# Sheet1.net
KiCad netlist of a schematic drawn in Altium Designer
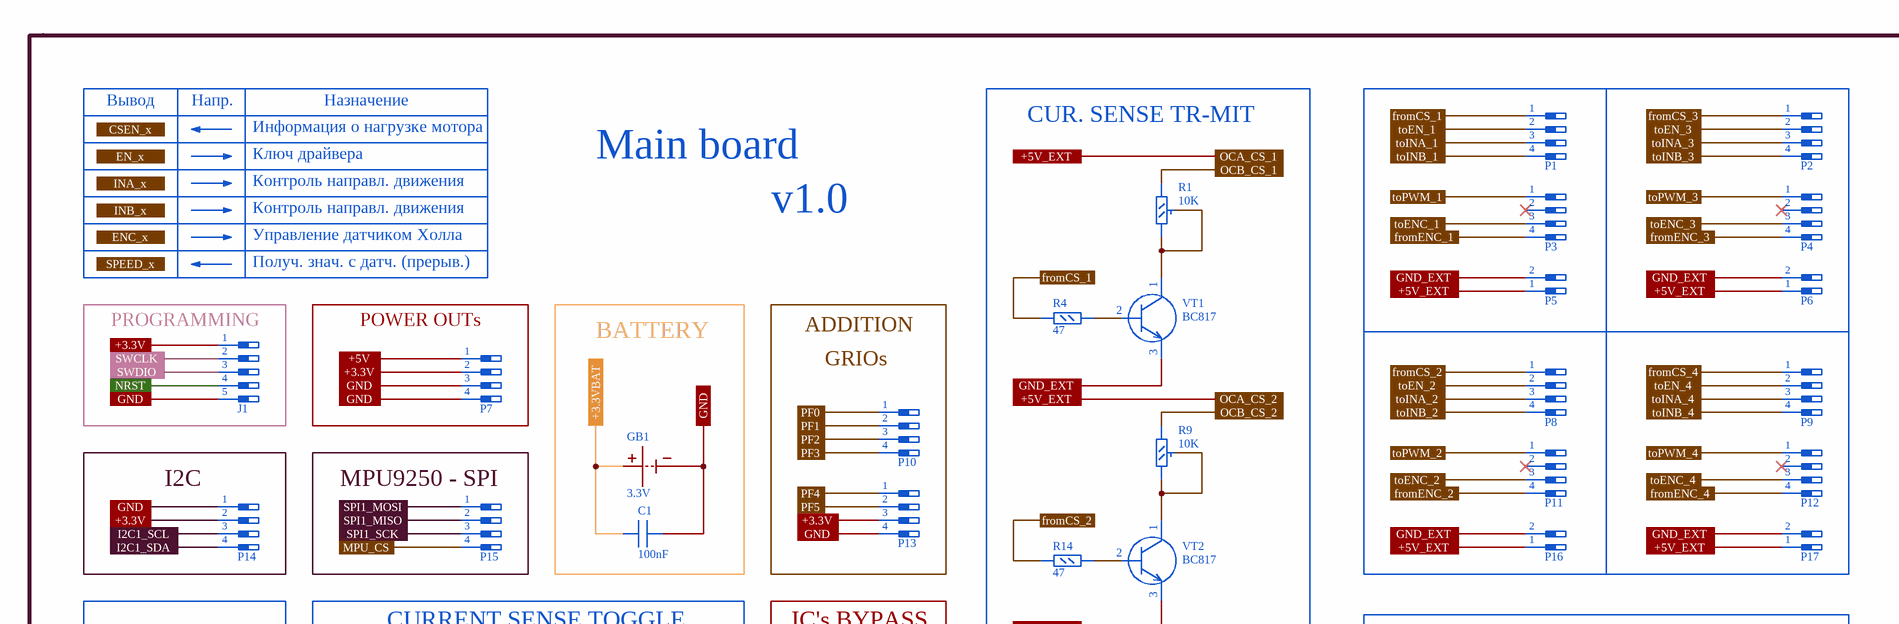
[diagram p0: Sheet1.SchDoc, top left]
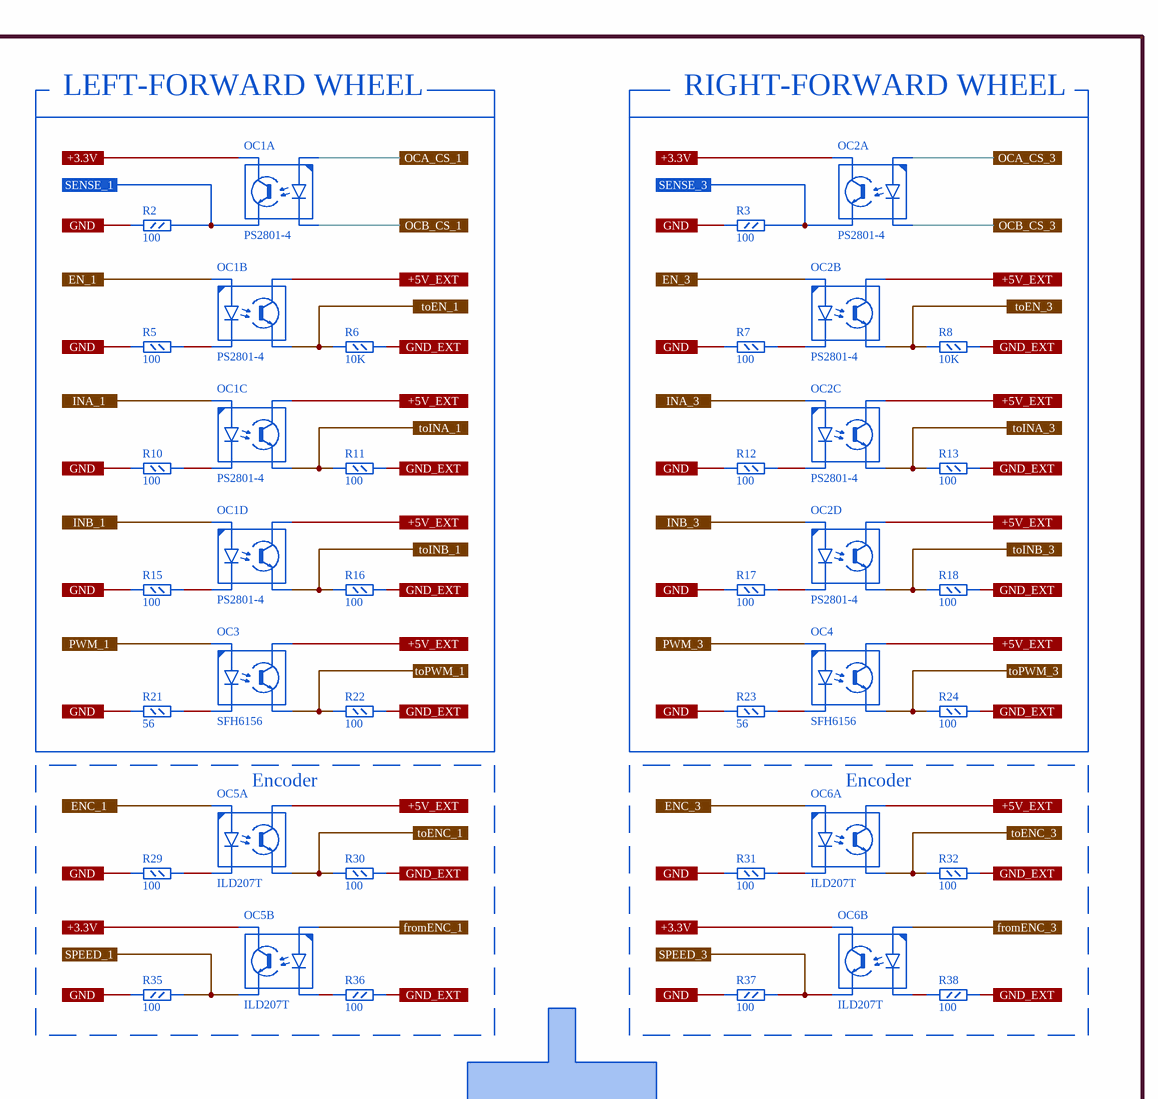
[diagram p1: Sheet1.SchDoc, top right]
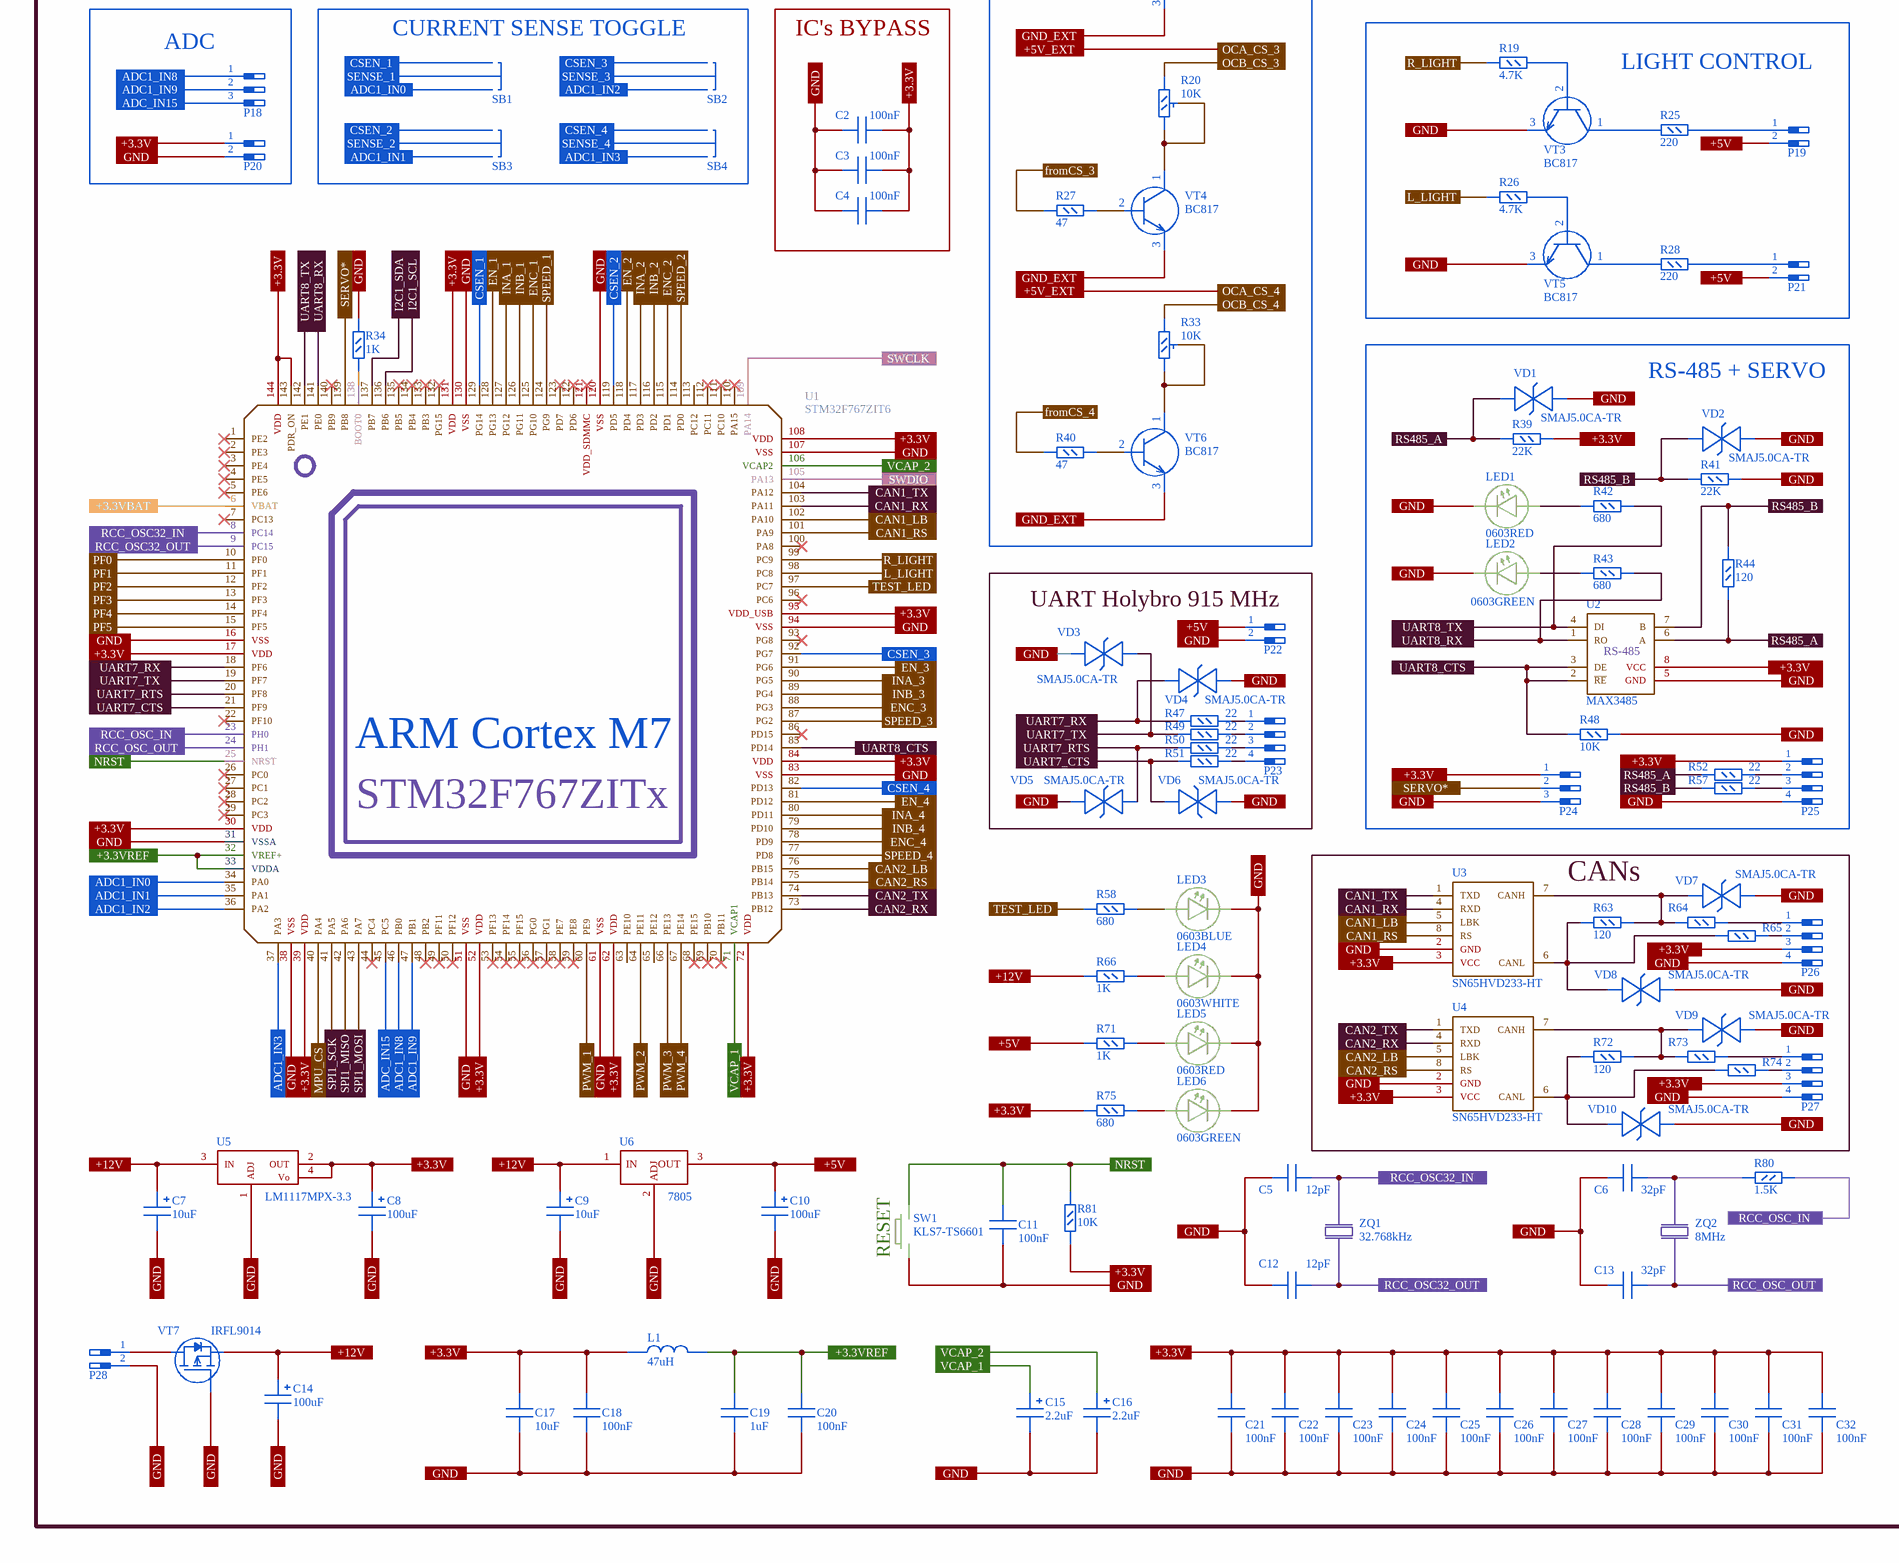
[diagram p2: Sheet1.SchDoc, bottom left]
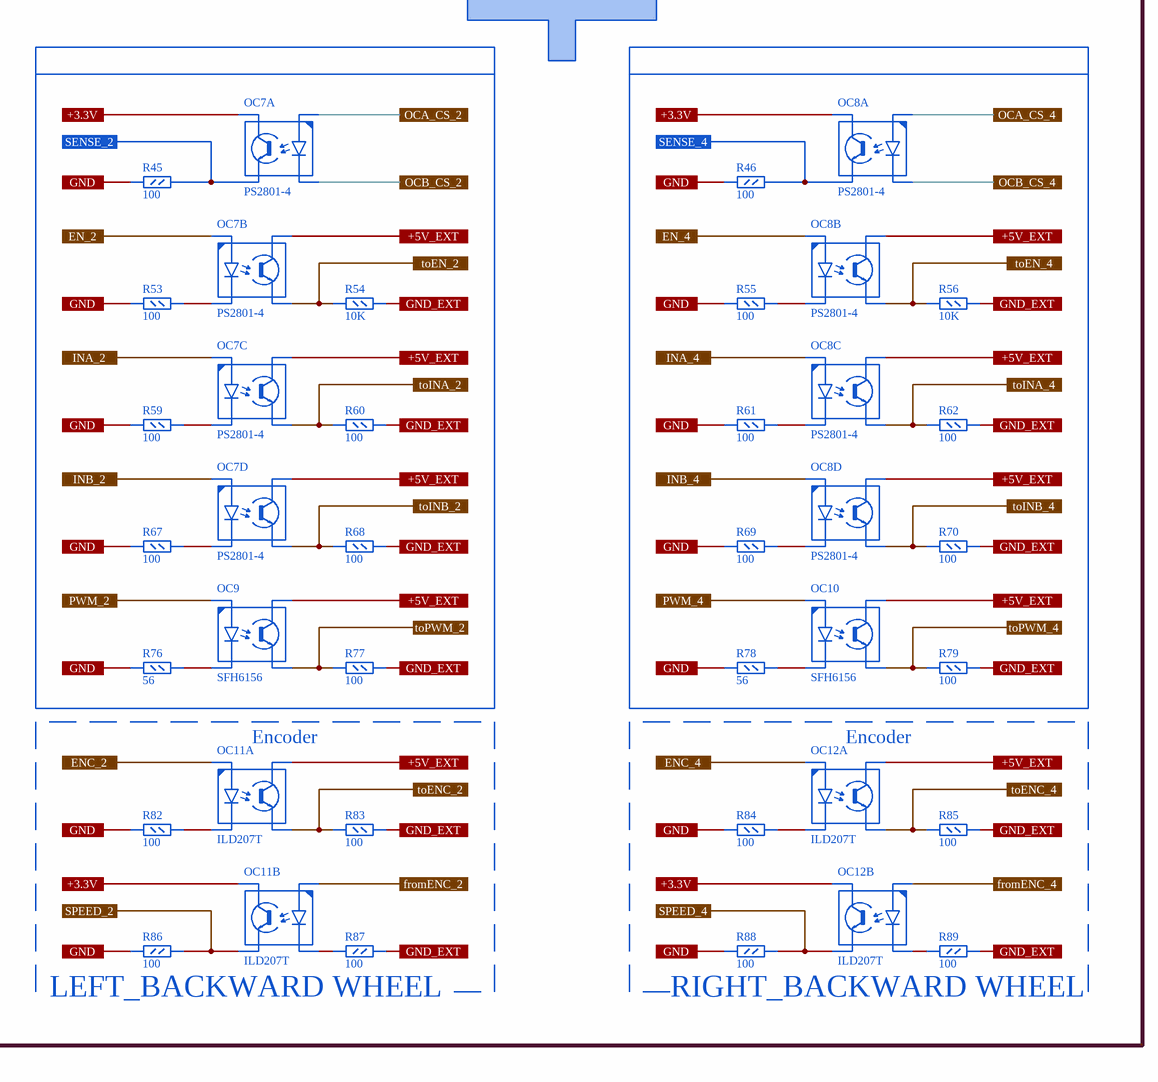
[diagram p3: Sheet1.SchDoc, bottom right]

(export (version "E")
  (design (tool "Eeschema 10.0.6"))
  (components
    (comp (ref "C1") (value "100nF") (footprint "C0603") (libsource (lib "CustomMillLib_Col") (part "Cap")))
    (comp (ref "C2") (value "100nF") (footprint "C0603") (libsource (lib "CustomMillLib_Col") (part "Cap")))
    (comp (ref "C3") (value "100nF") (footprint "C0603") (libsource (lib "CustomMillLib_Col") (part "Cap")))
    (comp (ref "C4") (value "100nF") (footprint "C0603") (libsource (lib "CustomMillLib_Col") (part "Cap")))
    (comp (ref "C5") (value "12pF") (footprint "C0603") (libsource (lib "CustomMillLib_Col") (part "Cap")))
    (comp (ref "C6") (value "32pF") (footprint "C0603") (libsource (lib "CustomMillLib_Col") (part "Cap")))
    (comp (ref "C7")
      (value "10uF")
      (footprint "CAP-ALSMD-4x5.4")
      (libsource (lib "CustomMillLib_Col") (part "Cap_Pol"))
    )
    (comp (ref "C8")
      (value "100uF")
      (footprint "CAP-ALSMD-6.3x5.4")
      (libsource (lib "CustomMillLib_Col") (part "Cap_Pol"))
    )
    (comp (ref "C9")
      (value "10uF")
      (footprint "CAP-ALSMD-4x5.4")
      (libsource (lib "CustomMillLib_Col") (part "Cap_Pol"))
    )
    (comp (ref "C10")
      (value "100uF")
      (footprint "CAP-ALSMD-6.3x5.4")
      (libsource (lib "CustomMillLib_Col") (part "Cap_Pol"))
    )
    (comp (ref "C11") (value "100nF") (footprint "C0603") (libsource (lib "CustomMillLib_Col") (part "Cap")))
    (comp (ref "C12") (value "12pF") (footprint "C0603") (libsource (lib "CustomMillLib_Col") (part "Cap")))
    (comp (ref "C13") (value "32pF") (footprint "C0603") (libsource (lib "CustomMillLib_Col") (part "Cap")))
    (comp (ref "C14")
      (value "100uF")
      (footprint "CAP-ALSMD-6.3x5.4")
      (libsource (lib "CustomMillLib_Col") (part "Cap_Pol"))
    )
    (comp (ref "C15")
      (value "2.2uF")
      (footprint "CAP-ALSMD-4x5.4")
      (libsource (lib "CustomMillLib_Col") (part "Cap_Pol"))
    )
    (comp (ref "C16")
      (value "2.2uF")
      (footprint "CAP-ALSMD-4x5.4")
      (libsource (lib "CustomMillLib_Col") (part "Cap_Pol"))
    )
    (comp (ref "C17") (value "10uF") (footprint "C0805") (libsource (lib "CustomMillLib_Col") (part "Cap")))
    (comp (ref "C18") (value "100nF") (footprint "C0603") (libsource (lib "CustomMillLib_Col") (part "Cap")))
    (comp (ref "C19") (value "1uF") (footprint "C0805") (libsource (lib "CustomMillLib_Col") (part "Cap")))
    (comp (ref "C20") (value "100nF") (footprint "C0603") (libsource (lib "CustomMillLib_Col") (part "Cap")))
    (comp (ref "C21") (value "100nF") (footprint "C0603") (libsource (lib "CustomMillLib_Col") (part "Cap")))
    (comp (ref "C22") (value "100nF") (footprint "C0603") (libsource (lib "CustomMillLib_Col") (part "Cap")))
    (comp (ref "C23") (value "100nF") (footprint "C0603") (libsource (lib "CustomMillLib_Col") (part "Cap")))
    (comp (ref "C24") (value "100nF") (footprint "C0603") (libsource (lib "CustomMillLib_Col") (part "Cap")))
    (comp (ref "C25") (value "100nF") (footprint "C0603") (libsource (lib "CustomMillLib_Col") (part "Cap")))
    (comp (ref "C26") (value "100nF") (footprint "C0603") (libsource (lib "CustomMillLib_Col") (part "Cap")))
    (comp (ref "C27") (value "100nF") (footprint "C0603") (libsource (lib "CustomMillLib_Col") (part "Cap")))
    (comp (ref "C28") (value "100nF") (footprint "C0603") (libsource (lib "CustomMillLib_Col") (part "Cap")))
    (comp (ref "C29") (value "100nF") (footprint "C0603") (libsource (lib "CustomMillLib_Col") (part "Cap")))
    (comp (ref "C30") (value "100nF") (footprint "C0603") (libsource (lib "CustomMillLib_Col") (part "Cap")))
    (comp (ref "C31") (value "100nF") (footprint "C0603") (libsource (lib "CustomMillLib_Col") (part "Cap")))
    (comp (ref "C32") (value "100nF") (footprint "C0603") (libsource (lib "CustomMillLib_Col") (part "Cap")))
    (comp (ref "GB1")
      (value "3.3V")
      (footprint "CR1616-SMD")
      (libsource (lib "PowerSupplies_Col") (part "Battery"))
    )
    (comp (ref "J1") (value "1x05") (footprint "5X1F") (libsource (lib "Connectors_Col") (part "1x05")))
    (comp (ref "L1")
      (value "47uH")
      (footprint "L0805")
      (libsource (lib "CustomMillLib_Col") (part "Inductor"))
    )
    (comp (ref "LED1")
      (value "0603RED")
      (footprint "LED0603")
      (libsource (lib "CustomMillLib_Col") (part "LED"))
    )
    (comp (ref "LED2")
      (value "0603GREEN")
      (footprint "LED0603")
      (libsource (lib "CustomMillLib_Col") (part "LED"))
    )
    (comp (ref "LED3")
      (value "0603BLUE")
      (footprint "LED0603")
      (libsource (lib "CustomMillLib_Col") (part "LED"))
    )
    (comp (ref "LED4")
      (value "0603WHITE")
      (footprint "LED0603")
      (libsource (lib "CustomMillLib_Col") (part "LED"))
    )
    (comp (ref "LED5")
      (value "0603RED")
      (footprint "LED0603")
      (libsource (lib "CustomMillLib_Col") (part "LED"))
    )
    (comp (ref "LED6")
      (value "0603GREEN")
      (footprint "LED0603")
      (libsource (lib "CustomMillLib_Col") (part "LED"))
    )
    (comp (ref "OC1") (value "PS2801-4") (footprint "SOP16") (libsource (lib "") (part "Optocoupler-4_1")))
    (comp (ref "OC2")
      (value "PS2801-4")
      (footprint "SOP16")
      (libsource (lib "CustomMillLib_Col") (part "Optocoupler-4"))
    )
    (comp (ref "OC3")
      (value "SFH6156")
      (footprint "SMD-4 (WIDE PINS)")
      (libsource (lib "CustomMillLib_Col") (part "Optocoupler"))
    )
    (comp (ref "OC4")
      (value "SFH6156")
      (footprint "SMD-4 (WIDE PINS)")
      (libsource (lib "CustomMillLib_Col") (part "Optocoupler"))
    )
    (comp (ref "OC5") (value "ILD207T") (footprint "SOIC8") (libsource (lib "") (part "Optocoupler-2_1")))
    (comp (ref "OC6")
      (value "ILD207T")
      (footprint "SOIC8")
      (libsource (lib "CustomMillLib_Col") (part "Optocoupler-2"))
    )
    (comp (ref "OC7") (value "PS2801-4") (footprint "SOP16") (libsource (lib "") (part "Optocoupler-4_1")))
    (comp (ref "OC8") (value "PS2801-4") (footprint "SOP16") (libsource (lib "") (part "Optocoupler-4_1")))
    (comp (ref "OC9")
      (value "SFH6156")
      (footprint "SMD-4 (WIDE PINS)")
      (libsource (lib "CustomMillLib_Col") (part "Optocoupler"))
    )
    (comp (ref "OC10")
      (value "SFH6156")
      (footprint "SMD-4 (WIDE PINS)")
      (libsource (lib "CustomMillLib_Col") (part "Optocoupler"))
    )
    (comp (ref "OC11")
      (value "ILD207T")
      (footprint "SOIC8")
      (libsource (lib "CustomMillLib_Col") (part "Optocoupler-2"))
    )
    (comp (ref "OC12") (value "ILD207T") (footprint "SOIC8") (libsource (lib "") (part "Optocoupler-2_1")))
    (comp (ref "P1")
      (value "1x04")
      (footprint "CWF-4R-2.50")
      (libsource (lib "Connectors_Col") (part "1x04"))
    )
    (comp (ref "P2")
      (value "1x04")
      (footprint "CWF-4R-2.50")
      (libsource (lib "Connectors_Col") (part "1x04"))
    )
    (comp (ref "P3")
      (value "1x04")
      (footprint "CWF-4R-2.50")
      (libsource (lib "Connectors_Col") (part "1x04"))
    )
    (comp (ref "P4")
      (value "1x04")
      (footprint "CWF-4R-2.50")
      (libsource (lib "Connectors_Col") (part "1x04"))
    )
    (comp (ref "P5") (value "1x02") (footprint "H2-5.08") (libsource (lib "Connectors_Col") (part "1x02")))
    (comp (ref "P6") (value "1x02") (footprint "H2-5.08") (libsource (lib "Connectors_Col") (part "1x02")))
    (comp (ref "P7")
      (value "1x04")
      (footprint "XH2.54-4PIN")
      (libsource (lib "Connectors_Col") (part "1x04"))
    )
    (comp (ref "P8")
      (value "1x04")
      (footprint "CWF-4R-2.50")
      (libsource (lib "Connectors_Col") (part "1x04"))
    )
    (comp (ref "P9")
      (value "1x04")
      (footprint "CWF-4R-2.50")
      (libsource (lib "Connectors_Col") (part "1x04"))
    )
    (comp (ref "P10")
      (value "1x04")
      (footprint "XH2.54-4PIN")
      (libsource (lib "Connectors_Col") (part "1x04"))
    )
    (comp (ref "P11")
      (value "1x04")
      (footprint "CWF-4R-2.50")
      (libsource (lib "Connectors_Col") (part "1x04"))
    )
    (comp (ref "P12")
      (value "1x04")
      (footprint "CWF-4R-2.50")
      (libsource (lib "Connectors_Col") (part "1x04"))
    )
    (comp (ref "P13")
      (value "1x04")
      (footprint "XH2.54-4PIN")
      (libsource (lib "Connectors_Col") (part "1x04"))
    )
    (comp (ref "P14")
      (value "1x04")
      (footprint "XH2.54-4PIN")
      (libsource (lib "Connectors_Col") (part "1x04"))
    )
    (comp (ref "P15")
      (value "1x04")
      (footprint "XH2.54-4PIN")
      (libsource (lib "Connectors_Col") (part "1x04"))
    )
    (comp (ref "P16") (value "1x02") (footprint "H2-5.08") (libsource (lib "Connectors_Col") (part "1x02")))
    (comp (ref "P17") (value "1x02") (footprint "H2-5.08") (libsource (lib "Connectors_Col") (part "1x02")))
    (comp (ref "P18")
      (value "1x03")
      (footprint "XH2.54-3PIN")
      (libsource (lib "Connectors_Col") (part "1x03"))
    )
    (comp (ref "P19")
      (value "1x02")
      (footprint "XH2.54-2PIN")
      (libsource (lib "Connectors_Col") (part "1x02"))
    )
    (comp (ref "P20")
      (value "1x02")
      (footprint "XH2.54-2PIN")
      (libsource (lib "Connectors_Col") (part "1x02"))
    )
    (comp (ref "P21")
      (value "1x02")
      (footprint "XH2.54-2PIN")
      (libsource (lib "Connectors_Col") (part "1x02"))
    )
    (comp (ref "P22")
      (value "1x02")
      (footprint "XH2.54-2PIN")
      (libsource (lib "Connectors_Col") (part "1x02"))
    )
    (comp (ref "P23")
      (value "1x04")
      (footprint "XH2.54-4PIN")
      (libsource (lib "Connectors_Col") (part "1x04"))
    )
    (comp (ref "P24")
      (value "1x03")
      (footprint "XH2.54-3PIN")
      (libsource (lib "Connectors_Col") (part "1x03"))
    )
    (comp (ref "P25")
      (value "1x04")
      (footprint "XH2.54-4PIN")
      (libsource (lib "Connectors_Col") (part "1x04"))
    )
    (comp (ref "P26")
      (value "1x04")
      (footprint "XH2.54-4PIN")
      (libsource (lib "Connectors_Col") (part "1x04"))
    )
    (comp (ref "P27")
      (value "1x04")
      (footprint "XH2.54-4PIN")
      (libsource (lib "Connectors_Col") (part "1x04"))
    )
    (comp (ref "P28") (value "1x02") (footprint "H2-5.08") (libsource (lib "Connectors_Col") (part "1x02")))
    (comp (ref "R1") (value "10K") (footprint "EVM3") (libsource (lib "CustomMillLib_Col") (part "Res Adj")))
    (comp (ref "R2") (value "100") (footprint "R0603") (libsource (lib "CustomMillLib_Col") (part "Res")))
    (comp (ref "R3") (value "100") (footprint "R0603") (libsource (lib "CustomMillLib_Col") (part "Res")))
    (comp (ref "R4") (value "47") (footprint "R0805") (libsource (lib "CustomMillLib_Col") (part "Res")))
    (comp (ref "R5") (value "100") (footprint "R0603") (libsource (lib "CustomMillLib_Col") (part "Res")))
    (comp (ref "R6") (value "10K") (footprint "R0603") (libsource (lib "CustomMillLib_Col") (part "Res")))
    (comp (ref "R7") (value "100") (footprint "R0603") (libsource (lib "CustomMillLib_Col") (part "Res")))
    (comp (ref "R8") (value "10K") (footprint "R0603") (libsource (lib "CustomMillLib_Col") (part "Res")))
    (comp (ref "R9") (value "10K") (footprint "EVM3") (libsource (lib "CustomMillLib_Col") (part "Res Adj")))
    (comp (ref "R10") (value "100") (footprint "R0603") (libsource (lib "CustomMillLib_Col") (part "Res")))
    (comp (ref "R11") (value "100") (footprint "R0603") (libsource (lib "CustomMillLib_Col") (part "Res")))
    (comp (ref "R12") (value "100") (footprint "R0603") (libsource (lib "CustomMillLib_Col") (part "Res")))
    (comp (ref "R13") (value "100") (footprint "R0603") (libsource (lib "CustomMillLib_Col") (part "Res")))
    (comp (ref "R14") (value "47") (footprint "R0805") (libsource (lib "CustomMillLib_Col") (part "Res")))
    (comp (ref "R15") (value "100") (footprint "R0603") (libsource (lib "CustomMillLib_Col") (part "Res")))
    (comp (ref "R16") (value "100") (footprint "R0603") (libsource (lib "CustomMillLib_Col") (part "Res")))
    (comp (ref "R17") (value "100") (footprint "R0603") (libsource (lib "CustomMillLib_Col") (part "Res")))
    (comp (ref "R18") (value "100") (footprint "R0603") (libsource (lib "CustomMillLib_Col") (part "Res")))
    (comp (ref "R19") (value "4.7K") (footprint "R0603") (libsource (lib "CustomMillLib_Col") (part "Res")))
    (comp (ref "R20") (value "10K") (footprint "EVM3") (libsource (lib "CustomMillLib_Col") (part "Res Adj")))
    (comp (ref "R21") (value "56") (footprint "R0805") (libsource (lib "CustomMillLib_Col") (part "Res")))
    (comp (ref "R22") (value "100") (footprint "R0603") (libsource (lib "CustomMillLib_Col") (part "Res")))
    (comp (ref "R23") (value "56") (footprint "R0805") (libsource (lib "CustomMillLib_Col") (part "Res")))
    (comp (ref "R24") (value "100") (footprint "R0603") (libsource (lib "CustomMillLib_Col") (part "Res")))
    (comp (ref "R25") (value "220") (footprint "R0603") (libsource (lib "CustomMillLib_Col") (part "Res")))
    (comp (ref "R26") (value "4.7K") (footprint "R0603") (libsource (lib "CustomMillLib_Col") (part "Res")))
    (comp (ref "R27") (value "47") (footprint "R0805") (libsource (lib "CustomMillLib_Col") (part "Res")))
    (comp (ref "R28") (value "220") (footprint "R0603") (libsource (lib "CustomMillLib_Col") (part "Res")))
    (comp (ref "R29") (value "100") (footprint "R0603") (libsource (lib "CustomMillLib_Col") (part "Res")))
    (comp (ref "R30") (value "100") (footprint "R0603") (libsource (lib "CustomMillLib_Col") (part "Res")))
    (comp (ref "R31") (value "100") (footprint "R0603") (libsource (lib "CustomMillLib_Col") (part "Res")))
    (comp (ref "R32") (value "100") (footprint "R0603") (libsource (lib "CustomMillLib_Col") (part "Res")))
    (comp (ref "R33") (value "10K") (footprint "EVM3") (libsource (lib "CustomMillLib_Col") (part "Res Adj")))
    (comp (ref "R34") (value "1K") (footprint "R0603") (libsource (lib "CustomMillLib_Col") (part "Res")))
    (comp (ref "R35") (value "100") (footprint "R0603") (libsource (lib "CustomMillLib_Col") (part "Res")))
    (comp (ref "R36") (value "100") (footprint "R0603") (libsource (lib "CustomMillLib_Col") (part "Res")))
    (comp (ref "R37") (value "100") (footprint "R0603") (libsource (lib "CustomMillLib_Col") (part "Res")))
    (comp (ref "R38") (value "100") (footprint "R0603") (libsource (lib "CustomMillLib_Col") (part "Res")))
    (comp (ref "R39") (value "22K") (footprint "R0603") (libsource (lib "CustomMillLib_Col") (part "Res")))
    (comp (ref "R40") (value "47") (footprint "R0805") (libsource (lib "CustomMillLib_Col") (part "Res")))
    (comp (ref "R41") (value "22K") (footprint "R0603") (libsource (lib "CustomMillLib_Col") (part "Res")))
    (comp (ref "R42") (value "680") (footprint "R0603") (libsource (lib "CustomMillLib_Col") (part "Res")))
    (comp (ref "R43") (value "680") (footprint "R0603") (libsource (lib "CustomMillLib_Col") (part "Res")))
    (comp (ref "R44") (value "120") (footprint "R0603") (libsource (lib "CustomMillLib_Col") (part "Res")))
    (comp (ref "R45") (value "100") (footprint "R0603") (libsource (lib "CustomMillLib_Col") (part "Res")))
    (comp (ref "R46") (value "100") (footprint "R0603") (libsource (lib "CustomMillLib_Col") (part "Res")))
    (comp (ref "R47") (value "22") (footprint "R0805") (libsource (lib "CustomMillLib_Col") (part "Res")))
    (comp (ref "R48") (value "10K") (footprint "R0603") (libsource (lib "CustomMillLib_Col") (part "Res")))
    (comp (ref "R49") (value "22") (footprint "R0805") (libsource (lib "CustomMillLib_Col") (part "Res")))
    (comp (ref "R50") (value "22") (footprint "R0805") (libsource (lib "CustomMillLib_Col") (part "Res")))
    (comp (ref "R51") (value "22") (footprint "R0805") (libsource (lib "CustomMillLib_Col") (part "Res")))
    (comp (ref "R52") (value "22") (footprint "R0805") (libsource (lib "CustomMillLib_Col") (part "Res")))
    (comp (ref "R53") (value "100") (footprint "R0603") (libsource (lib "CustomMillLib_Col") (part "Res")))
    (comp (ref "R54") (value "10K") (footprint "R0603") (libsource (lib "CustomMillLib_Col") (part "Res")))
    (comp (ref "R55") (value "100") (footprint "R0603") (libsource (lib "CustomMillLib_Col") (part "Res")))
    (comp (ref "R56") (value "10K") (footprint "R0603") (libsource (lib "CustomMillLib_Col") (part "Res")))
    (comp (ref "R57") (value "22") (footprint "R0805") (libsource (lib "CustomMillLib_Col") (part "Res")))
    (comp (ref "R58") (value "680") (footprint "R0603") (libsource (lib "CustomMillLib_Col") (part "Res")))
    (comp (ref "R59") (value "100") (footprint "R0603") (libsource (lib "CustomMillLib_Col") (part "Res")))
    (comp (ref "R60") (value "100") (footprint "R0603") (libsource (lib "CustomMillLib_Col") (part "Res")))
    (comp (ref "R61") (value "100") (footprint "R0603") (libsource (lib "CustomMillLib_Col") (part "Res")))
    (comp (ref "R62") (value "100") (footprint "R0603") (libsource (lib "CustomMillLib_Col") (part "Res")))
    (comp (ref "R63") (value "120") (footprint "R0603") (libsource (lib "CustomMillLib_Col") (part "Res")))
    (comp (ref "R64") (value "22") (footprint "R0805") (libsource (lib "CustomMillLib_Col") (part "Res")))
    (comp (ref "R65") (value "22") (footprint "R0805") (libsource (lib "CustomMillLib_Col") (part "Res")))
    (comp (ref "R66") (value "1K") (footprint "R0603") (libsource (lib "CustomMillLib_Col") (part "Res")))
    (comp (ref "R67") (value "100") (footprint "R0603") (libsource (lib "CustomMillLib_Col") (part "Res")))
    (comp (ref "R68") (value "100") (footprint "R0603") (libsource (lib "CustomMillLib_Col") (part "Res")))
    (comp (ref "R69") (value "100") (footprint "R0603") (libsource (lib "CustomMillLib_Col") (part "Res")))
    (comp (ref "R70") (value "100") (footprint "R0603") (libsource (lib "CustomMillLib_Col") (part "Res")))
    (comp (ref "R71") (value "1K") (footprint "R0603") (libsource (lib "CustomMillLib_Col") (part "Res")))
    (comp (ref "R72") (value "120") (footprint "R0603") (libsource (lib "CustomMillLib_Col") (part "Res")))
    (comp (ref "R73") (value "22") (footprint "R0805") (libsource (lib "CustomMillLib_Col") (part "Res")))
    (comp (ref "R74") (value "22") (footprint "R0805") (libsource (lib "CustomMillLib_Col") (part "Res")))
    (comp (ref "R75") (value "680") (footprint "R0603") (libsource (lib "CustomMillLib_Col") (part "Res")))
    (comp (ref "R76") (value "56") (footprint "R0805") (libsource (lib "CustomMillLib_Col") (part "Res")))
    (comp (ref "R77") (value "100") (footprint "R0603") (libsource (lib "CustomMillLib_Col") (part "Res")))
    (comp (ref "R78") (value "56") (footprint "R0805") (libsource (lib "CustomMillLib_Col") (part "Res")))
    (comp (ref "R79") (value "100") (footprint "R0603") (libsource (lib "CustomMillLib_Col") (part "Res")))
    (comp (ref "R80") (value "1.5K") (footprint "R0603") (libsource (lib "CustomMillLib_Col") (part "Res")))
    (comp (ref "R81") (value "10K") (footprint "R0603") (libsource (lib "CustomMillLib_Col") (part "Res")))
    (comp (ref "R82") (value "100") (footprint "R0603") (libsource (lib "CustomMillLib_Col") (part "Res")))
    (comp (ref "R83") (value "100") (footprint "R0603") (libsource (lib "CustomMillLib_Col") (part "Res")))
    (comp (ref "R84") (value "100") (footprint "R0603") (libsource (lib "CustomMillLib_Col") (part "Res")))
    (comp (ref "R85") (value "100") (footprint "R0603") (libsource (lib "CustomMillLib_Col") (part "Res")))
    (comp (ref "R86") (value "100") (footprint "R0603") (libsource (lib "CustomMillLib_Col") (part "Res")))
    (comp (ref "R87") (value "100") (footprint "R0603") (libsource (lib "CustomMillLib_Col") (part "Res")))
    (comp (ref "R88") (value "100") (footprint "R0603") (libsource (lib "CustomMillLib_Col") (part "Res")))
    (comp (ref "R89") (value "100") (footprint "R0603") (libsource (lib "CustomMillLib_Col") (part "Res")))
    (comp (ref "SB1")
      (value "Soldier Toggle")
      (footprint "SOLDBR-3")
      (libsource (lib "CustomMillLib_Col") (part "Soldier Toggle"))
    )
    (comp (ref "SB2")
      (value "Soldier Toggle")
      (footprint "SOLDBR-3")
      (libsource (lib "CustomMillLib_Col") (part "Soldier Toggle"))
    )
    (comp (ref "SB3")
      (value "Soldier Toggle")
      (footprint "SOLDBR-3")
      (libsource (lib "CustomMillLib_Col") (part "Soldier Toggle"))
    )
    (comp (ref "SB4")
      (value "Soldier Toggle")
      (footprint "SOLDBR-3")
      (libsource (lib "CustomMillLib_Col") (part "Soldier Toggle"))
    )
    (comp (ref "SW1")
      (value "KLS7-TS6601")
      (footprint "BUT6.5X4.5")
      (libsource (lib "CustomMillLib_Col") (part "Button_2"))
    )
    (comp (ref "U1")
      (value "STM32F767ZIT6")
      (footprint "LQFP144")
      (libsource (lib "STM32Lib_Col") (part "STM32F767ZITx"))
    )
    (comp (ref "U2")
      (value "MAX3485")
      (footprint "SOIC8")
      (description "Driver RS-485")
      (libsource (lib "DigitalUnitsLib_Col") (part "MAX485"))
    )
    (comp (ref "U3")
      (value "SN65HVD233-HT")
      (footprint "SOIC8")
      (description "3.3-V CAN Transceiver")
      (libsource (lib "DigitalUnitsLib_Col") (part "SN65HVD233"))
    )
    (comp (ref "U4")
      (value "SN65HVD233-HT")
      (footprint "SOIC8")
      (description "3.3-V CAN Transceiver")
      (libsource (lib "DigitalUnitsLib_Col") (part "SN65HVD233"))
    )
    (comp (ref "U5")
      (value "LM1117MPX-3.3")
      (footprint "SOT-223")
      (libsource (lib "PowerSupplies_Col") (part "LM1117"))
    )
    (comp (ref "U6") (value "7805") (footprint "D2PAK") (libsource (lib "PowerSupplies_Col") (part "LM7805")))
    (comp (ref "VD1")
      (value "SMAJ5.0CA-TR")
      (footprint "SMA")
      (libsource (lib "CustomMillLib_Col") (part "Suppressor_bi-Dir"))
    )
    (comp (ref "VD2")
      (value "SMAJ5.0CA-TR")
      (footprint "SMA")
      (libsource (lib "CustomMillLib_Col") (part "Suppressor_bi-Dir"))
    )
    (comp (ref "VD3")
      (value "SMAJ5.0CA-TR")
      (footprint "SMA")
      (libsource (lib "CustomMillLib_Col") (part "Suppressor_bi-Dir"))
    )
    (comp (ref "VD4")
      (value "SMAJ5.0CA-TR")
      (footprint "SMA")
      (libsource (lib "CustomMillLib_Col") (part "Suppressor_bi-Dir"))
    )
    (comp (ref "VD5")
      (value "SMAJ5.0CA-TR")
      (footprint "SMA")
      (libsource (lib "CustomMillLib_Col") (part "Suppressor_bi-Dir"))
    )
    (comp (ref "VD6")
      (value "SMAJ5.0CA-TR")
      (footprint "SMA")
      (libsource (lib "CustomMillLib_Col") (part "Suppressor_bi-Dir"))
    )
    (comp (ref "VD7")
      (value "SMAJ5.0CA-TR")
      (footprint "SMA")
      (libsource (lib "CustomMillLib_Col") (part "Suppressor_bi-Dir"))
    )
    (comp (ref "VD8")
      (value "SMAJ5.0CA-TR")
      (footprint "SMA")
      (libsource (lib "CustomMillLib_Col") (part "Suppressor_bi-Dir"))
    )
    (comp (ref "VD9")
      (value "SMAJ5.0CA-TR")
      (footprint "SMA")
      (libsource (lib "CustomMillLib_Col") (part "Suppressor_bi-Dir"))
    )
    (comp (ref "VD10")
      (value "SMAJ5.0CA-TR")
      (footprint "SMA")
      (libsource (lib "CustomMillLib_Col") (part "Suppressor_bi-Dir"))
    )
    (comp (ref "VT1")
      (value "BC817")
      (footprint "SOT-23-1P")
      (libsource (lib "CustomMillLib_Col") (part "NPN_CBE"))
    )
    (comp (ref "VT2")
      (value "BC817")
      (footprint "SOT-23-1P")
      (libsource (lib "CustomMillLib_Col") (part "NPN_CBE"))
    )
    (comp (ref "VT3")
      (value "BC817")
      (footprint "SOT-23-1P")
      (libsource (lib "CustomMillLib_Col") (part "NPN_CBE"))
    )
    (comp (ref "VT4")
      (value "BC817")
      (footprint "SOT-23-1P")
      (libsource (lib "CustomMillLib_Col") (part "NPN_CBE"))
    )
    (comp (ref "VT5")
      (value "BC817")
      (footprint "SOT-23-1P")
      (libsource (lib "CustomMillLib_Col") (part "NPN_CBE"))
    )
    (comp (ref "VT6")
      (value "BC817")
      (footprint "SOT-23-1P")
      (libsource (lib "CustomMillLib_Col") (part "NPN_CBE"))
    )
    (comp (ref "VT7")
      (value "IRFL9014")
      (footprint "SOT-223-24")
      (libsource (lib "CustomMillLib_Col") (part "MOSFET-P"))
    )
    (comp (ref "ZQ1")
      (value "32.768kHz")
      (footprint "NX3215SA")
      (libsource (lib "CustomMillLib_Col") (part "Crystall"))
    )
    (comp (ref "ZQ2")
      (value "8MHz")
      (footprint "CRYSTALL-SMD")
      (libsource (lib "CustomMillLib_Col") (part "Crystall"))
    )
  )
  (nets
    (net (code "1") (name "/+3.3V") (class "Default")
      (node (ref "C17") (pin "2") (pinfunction "62_2") (pintype "passive"))
      (node (ref "C18") (pin "2") (pinfunction "62_2") (pintype "passive"))
      (node (ref "C2") (pin "2") (pinfunction "62_2") (pintype "passive"))
      (node (ref "C21") (pin "2") (pinfunction "62_2") (pintype "passive"))
      (node (ref "C22") (pin "2") (pinfunction "62_2") (pintype "passive"))
      (node (ref "C23") (pin "2") (pinfunction "62_2") (pintype "passive"))
      (node (ref "C24") (pin "2") (pinfunction "62_2") (pintype "passive"))
      (node (ref "C25") (pin "2") (pinfunction "62_2") (pintype "passive"))
      (node (ref "C26") (pin "2") (pinfunction "62_2") (pintype "passive"))
      (node (ref "C27") (pin "2") (pinfunction "62_2") (pintype "passive"))
      (node (ref "C28") (pin "2") (pinfunction "62_2") (pintype "passive"))
      (node (ref "C29") (pin "2") (pinfunction "62_2") (pintype "passive"))
      (node (ref "C3") (pin "2") (pinfunction "62_2") (pintype "passive"))
      (node (ref "C30") (pin "2") (pinfunction "62_2") (pintype "passive"))
      (node (ref "C31") (pin "2") (pinfunction "62_2") (pintype "passive"))
      (node (ref "C32") (pin "2") (pinfunction "62_2") (pintype "passive"))
      (node (ref "C4") (pin "2") (pinfunction "62_2") (pintype "passive"))
      (node (ref "C8") (pin "1") (pinfunction "61_1") (pintype "passive"))
      (node (ref "J1") (pin "1") (pintype "passive"))
      (node (ref "L1") (pin "1") (pinfunction "3_1") (pintype "passive"))
      (node (ref "OC1") (pin "16") (pinfunction "4_16") (pintype "passive"))
      (node (ref "OC11") (pin "6") (pinfunction "4_6") (pintype "passive"))
      (node (ref "OC12") (pin "6") (pinfunction "4_6") (pintype "passive"))
      (node (ref "OC2") (pin "16") (pinfunction "4_16") (pintype "passive"))
      (node (ref "OC5") (pin "6") (pinfunction "4_6") (pintype "passive"))
      (node (ref "OC6") (pin "6") (pinfunction "4_6") (pintype "passive"))
      (node (ref "OC7") (pin "16") (pinfunction "4_16") (pintype "passive"))
      (node (ref "OC8") (pin "16") (pinfunction "4_16") (pintype "passive"))
      (node (ref "P13") (pin "3") (pintype "passive"))
      (node (ref "P14") (pin "2") (pintype "passive"))
      (node (ref "P20") (pin "1") (pintype "passive"))
      (node (ref "P24") (pin "1") (pintype "passive"))
      (node (ref "P25") (pin "1") (pintype "passive"))
      (node (ref "P26") (pin "3") (pintype "passive"))
      (node (ref "P27") (pin "3") (pintype "passive"))
      (node (ref "P7") (pin "2") (pintype "passive"))
      (node (ref "R39") (pin "1") (pinfunction "2_1") (pintype "passive"))
      (node (ref "R75") (pin "2") (pinfunction "2_2") (pintype "passive"))
      (node (ref "R81") (pin "2") (pinfunction "2_2") (pintype "passive"))
      (node (ref "U1") (pin "108") (pinfunction "VDD_108") (pintype "passive"))
      (node (ref "U1") (pin "131") (pinfunction "VDD_131") (pintype "passive"))
      (node (ref "U1") (pin "143") (pinfunction "PDR_ON_143") (pintype "passive"))
      (node (ref "U1") (pin "144") (pinfunction "VDD_144") (pintype "passive"))
      (node (ref "U1") (pin "17") (pinfunction "VDD_17") (pintype "passive"))
      (node (ref "U1") (pin "30") (pinfunction "VDD_30") (pintype "passive"))
      (node (ref "U1") (pin "39") (pinfunction "VDD_39") (pintype "passive"))
      (node (ref "U1") (pin "52") (pinfunction "VDD_52") (pintype "passive"))
      (node (ref "U1") (pin "62") (pinfunction "VDD_62") (pintype "passive"))
      (node (ref "U1") (pin "72") (pinfunction "VDD_72") (pintype "passive"))
      (node (ref "U1") (pin "84") (pinfunction "VDD_84") (pintype "passive"))
      (node (ref "U1") (pin "95") (pinfunction "VDD_USB_95") (pintype "passive"))
      (node (ref "U2") (pin "8") (pinfunction "VCC_8") (pintype "passive"))
      (node (ref "U3") (pin "3") (pinfunction "VCC_3") (pintype "passive"))
      (node (ref "U4") (pin "3") (pinfunction "VCC_3") (pintype "passive"))
      (node (ref "U5") (pin "2") (pinfunction "OUT_2") (pintype "passive"))
      (node (ref "U5") (pin "4") (pinfunction "Vo_4") (pintype "passive"))
    )
    (net (code "2") (name "/+3.3VBAT") (class "Default")
      (node (ref "C1") (pin "1") (pinfunction "61_1") (pintype "passive"))
      (node (ref "GB1") (pin "2") (pintype "passive"))
      (node (ref "U1") (pin "6") (pinfunction "VBAT_6") (pintype "passive"))
    )
    (net (code "3") (name "/+3.3VREF") (class "Default")
      (node (ref "C19") (pin "2") (pinfunction "62_2") (pintype "passive"))
      (node (ref "C20") (pin "2") (pinfunction "62_2") (pintype "passive"))
      (node (ref "L1") (pin "2") (pinfunction "4_2") (pintype "passive"))
      (node (ref "U1") (pin "32") (pinfunction "VREF+_32") (pintype "passive"))
      (node (ref "U1") (pin "33") (pinfunction "VDDA_33") (pintype "passive"))
    )
    (net (code "4") (name "/+5V") (class "Default")
      (node (ref "C10") (pin "1") (pinfunction "61_1") (pintype "passive"))
      (node (ref "P19") (pin "2") (pintype "passive"))
      (node (ref "P21") (pin "2") (pintype "passive"))
      (node (ref "P22") (pin "1") (pintype "passive"))
      (node (ref "P7") (pin "1") (pintype "passive"))
      (node (ref "R71") (pin "2") (pinfunction "2_2") (pintype "passive"))
      (node (ref "U6") (pin "3") (pinfunction "OUT_3") (pintype "passive"))
    )
    (net (code "5") (name "/+5V_EXT") (class "Default")
      (node (ref "OC1") (pin "1") (pinfunction "1_1") (pintype "passive"))
      (node (ref "OC1") (pin "10") (pinfunction "4_10") (pintype "passive"))
      (node (ref "OC1") (pin "12") (pinfunction "4_12") (pintype "passive"))
      (node (ref "OC1") (pin "14") (pinfunction "4_14") (pintype "passive"))
      (node (ref "OC10") (pin "4") (pinfunction "4_4") (pintype "passive"))
      (node (ref "OC11") (pin "8") (pinfunction "4_8") (pintype "passive"))
      (node (ref "OC12") (pin "8") (pinfunction "4_8") (pintype "passive"))
      (node (ref "OC2") (pin "1") (pinfunction "1_1") (pintype "passive"))
      (node (ref "OC2") (pin "10") (pinfunction "4_10") (pintype "passive"))
      (node (ref "OC2") (pin "12") (pinfunction "4_12") (pintype "passive"))
      (node (ref "OC2") (pin "14") (pinfunction "4_14") (pintype "passive"))
      (node (ref "OC3") (pin "4") (pinfunction "4_4") (pintype "passive"))
      (node (ref "OC4") (pin "4") (pinfunction "4_4") (pintype "passive"))
      (node (ref "OC5") (pin "8") (pinfunction "4_8") (pintype "passive"))
      (node (ref "OC6") (pin "8") (pinfunction "4_8") (pintype "passive"))
      (node (ref "OC7") (pin "1") (pinfunction "1_1") (pintype "passive"))
      (node (ref "OC7") (pin "10") (pinfunction "4_10") (pintype "passive"))
      (node (ref "OC7") (pin "12") (pinfunction "4_12") (pintype "passive"))
      (node (ref "OC7") (pin "14") (pinfunction "4_14") (pintype "passive"))
      (node (ref "OC8") (pin "1") (pinfunction "1_1") (pintype "passive"))
      (node (ref "OC8") (pin "10") (pinfunction "4_10") (pintype "passive"))
      (node (ref "OC8") (pin "12") (pinfunction "4_12") (pintype "passive"))
      (node (ref "OC8") (pin "14") (pinfunction "4_14") (pintype "passive"))
      (node (ref "OC9") (pin "4") (pinfunction "4_4") (pintype "passive"))
      (node (ref "P16") (pin "1") (pintype "passive"))
      (node (ref "P17") (pin "1") (pintype "passive"))
      (node (ref "P5") (pin "1") (pintype "passive"))
      (node (ref "P6") (pin "1") (pintype "passive"))
    )
    (net (code "6") (name "/+12V") (class "Default")
      (node (ref "C14") (pin "1") (pinfunction "61_1") (pintype "passive"))
      (node (ref "C7") (pin "1") (pinfunction "61_1") (pintype "passive"))
      (node (ref "C9") (pin "1") (pinfunction "61_1") (pintype "passive"))
      (node (ref "R66") (pin "2") (pinfunction "2_2") (pintype "passive"))
      (node (ref "U5") (pin "3") (pinfunction "IN_3") (pintype "passive"))
      (node (ref "U6") (pin "1") (pinfunction "IN_1") (pintype "passive"))
      (node (ref "VT7") (pin "3") (pinfunction "S_3") (pintype "passive"))
    )
    (net (code "7") (name "/ADC1_IN0") (class "Default")
      (node (ref "SB1") (pin "3") (pintype "passive"))
      (node (ref "U1") (pin "34") (pinfunction "PA0_34") (pintype "passive"))
    )
    (net (code "8") (name "/ADC1_IN1") (class "Default")
      (node (ref "SB3") (pin "3") (pintype "passive"))
      (node (ref "U1") (pin "35") (pinfunction "PA1_35") (pintype "passive"))
    )
    (net (code "9") (name "/ADC1_IN2") (class "Default")
      (node (ref "SB2") (pin "3") (pintype "passive"))
      (node (ref "U1") (pin "36") (pinfunction "PA2_36") (pintype "passive"))
    )
    (net (code "10") (name "/ADC1_IN3") (class "Default")
      (node (ref "SB4") (pin "3") (pintype "passive"))
      (node (ref "U1") (pin "37") (pinfunction "PA3_37") (pintype "passive"))
    )
    (net (code "11") (name "/ADC1_IN8") (class "Default")
      (node (ref "P18") (pin "1") (pintype "passive"))
      (node (ref "U1") (pin "46") (pinfunction "PB0_46") (pintype "passive"))
    )
    (net (code "12") (name "/ADC1_IN9") (class "Default")
      (node (ref "P18") (pin "2") (pintype "passive"))
      (node (ref "U1") (pin "47") (pinfunction "PB1_47") (pintype "passive"))
    )
    (net (code "13") (name "/ADC_IN15") (class "Default")
      (node (ref "P18") (pin "3") (pintype "passive"))
      (node (ref "U1") (pin "45") (pinfunction "PC5_45") (pintype "passive"))
    )
    (net (code "14") (name "/CAN1_LB") (class "Default")
      (node (ref "U1") (pin "102") (pinfunction "PA10_102") (pintype "passive"))
      (node (ref "U3") (pin "5") (pinfunction "LBK_5") (pintype "passive"))
    )
    (net (code "15") (name "/CAN1_RS") (class "Default")
      (node (ref "U1") (pin "101") (pinfunction "PA9_101") (pintype "passive"))
      (node (ref "U3") (pin "8") (pinfunction "RS_8") (pintype "passive"))
    )
    (net (code "16") (name "/CAN1_RX") (class "Default")
      (node (ref "U1") (pin "103") (pinfunction "PA11_103") (pintype "passive"))
      (node (ref "U3") (pin "4") (pinfunction "RXD_4") (pintype "passive"))
    )
    (net (code "17") (name "/CAN1_TX") (class "Default")
      (node (ref "U1") (pin "104") (pinfunction "PA12_104") (pintype "passive"))
      (node (ref "U3") (pin "1") (pinfunction "TXD_1") (pintype "passive"))
    )
    (net (code "18") (name "/CAN2_LB") (class "Default")
      (node (ref "U1") (pin "76") (pinfunction "PB15_76") (pintype "passive"))
      (node (ref "U4") (pin "5") (pinfunction "LBK_5") (pintype "passive"))
    )
    (net (code "19") (name "/CAN2_RS") (class "Default")
      (node (ref "U1") (pin "75") (pinfunction "PB14_75") (pintype "passive"))
      (node (ref "U4") (pin "8") (pinfunction "RS_8") (pintype "passive"))
    )
    (net (code "20") (name "/CAN2_RX") (class "Default")
      (node (ref "U1") (pin "73") (pinfunction "PB12_73") (pintype "passive"))
      (node (ref "U4") (pin "4") (pinfunction "RXD_4") (pintype "passive"))
    )
    (net (code "21") (name "/CAN2_TX") (class "Default")
      (node (ref "U1") (pin "74") (pinfunction "PB13_74") (pintype "passive"))
      (node (ref "U4") (pin "1") (pinfunction "TXD_1") (pintype "passive"))
    )
    (net (code "22") (name "/CSEN_1") (class "Default")
      (node (ref "SB1") (pin "1") (pintype "passive"))
      (node (ref "U1") (pin "129") (pinfunction "PG14_129") (pintype "passive"))
    )
    (net (code "23") (name "/CSEN_2") (class "Default")
      (node (ref "SB3") (pin "1") (pintype "passive"))
      (node (ref "U1") (pin "119") (pinfunction "PD5_119") (pintype "passive"))
    )
    (net (code "24") (name "/CSEN_3") (class "Default")
      (node (ref "SB2") (pin "1") (pintype "passive"))
      (node (ref "U1") (pin "92") (pinfunction "PG7_92") (pintype "passive"))
    )
    (net (code "25") (name "/CSEN_4") (class "Default")
      (node (ref "SB4") (pin "1") (pintype "passive"))
      (node (ref "U1") (pin "82") (pinfunction "PD13_82") (pintype "passive"))
    )
    (net (code "27") (name "/ENC_1") (class "Default")
      (node (ref "OC5") (pin "1") (pinfunction "1_1") (pintype "passive"))
      (node (ref "U1") (pin "125") (pinfunction "PG10_125") (pintype "passive"))
    )
    (net (code "28") (name "/ENC_2") (class "Default")
      (node (ref "OC11") (pin "1") (pinfunction "1_1") (pintype "passive"))
      (node (ref "U1") (pin "115") (pinfunction "PD1_115") (pintype "passive"))
    )
    (net (code "29") (name "/ENC_3") (class "Default")
      (node (ref "OC6") (pin "1") (pinfunction "1_1") (pintype "passive"))
      (node (ref "U1") (pin "88") (pinfunction "PG3_88") (pintype "passive"))
    )
    (net (code "30") (name "/ENC_4") (class "Default")
      (node (ref "OC12") (pin "1") (pinfunction "1_1") (pintype "passive"))
      (node (ref "U1") (pin "78") (pinfunction "PD9_78") (pintype "passive"))
    )
    (net (code "32") (name "/EN_1") (class "Default")
      (node (ref "OC1") (pin "3") (pinfunction "1_3") (pintype "passive"))
      (node (ref "U1") (pin "128") (pinfunction "PG13_128") (pintype "passive"))
    )
    (net (code "33") (name "/EN_2") (class "Default")
      (node (ref "OC7") (pin "3") (pinfunction "1_3") (pintype "passive"))
      (node (ref "U1") (pin "118") (pinfunction "PD4_118") (pintype "passive"))
    )
    (net (code "34") (name "/EN_3") (class "Default")
      (node (ref "OC2") (pin "3") (pinfunction "1_3") (pintype "passive"))
      (node (ref "U1") (pin "91") (pinfunction "PG6_91") (pintype "passive"))
    )
    (net (code "35") (name "/EN_4") (class "Default")
      (node (ref "OC8") (pin "3") (pinfunction "1_3") (pintype "passive"))
      (node (ref "U1") (pin "81") (pinfunction "PD12_81") (pintype "passive"))
    )
    (net (code "37") (name "/GND") (class "Default")
      (node (ref "C1") (pin "2") (pinfunction "62_2") (pintype "passive"))
      (node (ref "C10") (pin "2") (pinfunction "62_2") (pintype "passive"))
      (node (ref "C11") (pin "1") (pinfunction "61_1") (pintype "passive"))
      (node (ref "C12") (pin "2") (pinfunction "62_2") (pintype "passive"))
      (node (ref "C13") (pin "2") (pinfunction "62_2") (pintype "passive"))
      (node (ref "C14") (pin "2") (pinfunction "62_2") (pintype "passive"))
      (node (ref "C15") (pin "2") (pinfunction "62_2") (pintype "passive"))
      (node (ref "C16") (pin "2") (pinfunction "62_2") (pintype "passive"))
      (node (ref "C17") (pin "1") (pinfunction "61_1") (pintype "passive"))
      (node (ref "C18") (pin "1") (pinfunction "61_1") (pintype "passive"))
      (node (ref "C19") (pin "1") (pinfunction "61_1") (pintype "passive"))
      (node (ref "C2") (pin "1") (pinfunction "61_1") (pintype "passive"))
      (node (ref "C20") (pin "1") (pinfunction "61_1") (pintype "passive"))
      (node (ref "C21") (pin "1") (pinfunction "61_1") (pintype "passive"))
      (node (ref "C22") (pin "1") (pinfunction "61_1") (pintype "passive"))
      (node (ref "C23") (pin "1") (pinfunction "61_1") (pintype "passive"))
      (node (ref "C24") (pin "1") (pinfunction "61_1") (pintype "passive"))
      (node (ref "C25") (pin "1") (pinfunction "61_1") (pintype "passive"))
      (node (ref "C26") (pin "1") (pinfunction "61_1") (pintype "passive"))
      (node (ref "C27") (pin "1") (pinfunction "61_1") (pintype "passive"))
      (node (ref "C28") (pin "1") (pinfunction "61_1") (pintype "passive"))
      (node (ref "C29") (pin "1") (pinfunction "61_1") (pintype "passive"))
      (node (ref "C3") (pin "1") (pinfunction "61_1") (pintype "passive"))
      (node (ref "C30") (pin "1") (pinfunction "61_1") (pintype "passive"))
      (node (ref "C31") (pin "1") (pinfunction "61_1") (pintype "passive"))
      (node (ref "C32") (pin "1") (pinfunction "61_1") (pintype "passive"))
      (node (ref "C4") (pin "1") (pinfunction "61_1") (pintype "passive"))
      (node (ref "C5") (pin "2") (pinfunction "62_2") (pintype "passive"))
      (node (ref "C6") (pin "2") (pinfunction "62_2") (pintype "passive"))
      (node (ref "C7") (pin "2") (pinfunction "62_2") (pintype "passive"))
      (node (ref "C8") (pin "2") (pinfunction "62_2") (pintype "passive"))
      (node (ref "C9") (pin "2") (pinfunction "62_2") (pintype "passive"))
      (node (ref "GB1") (pin "1") (pinfunction "+_1") (pintype "passive"))
      (node (ref "J1") (pin "5") (pintype "passive"))
      (node (ref "LED1") (pin "2") (pinfunction "6_2") (pintype "passive"))
      (node (ref "LED2") (pin "2") (pinfunction "6_2") (pintype "passive"))
      (node (ref "LED3") (pin "2") (pinfunction "6_2") (pintype "passive"))
      (node (ref "LED4") (pin "2") (pinfunction "6_2") (pintype "passive"))
      (node (ref "LED5") (pin "2") (pinfunction "6_2") (pintype "passive"))
      (node (ref "LED6") (pin "2") (pinfunction "6_2") (pintype "passive"))
      (node (ref "P13") (pin "4") (pintype "passive"))
      (node (ref "P14") (pin "1") (pintype "passive"))
      (node (ref "P20") (pin "2") (pintype "passive"))
      (node (ref "P22") (pin "2") (pintype "passive"))
      (node (ref "P24") (pin "3") (pintype "passive"))
      (node (ref "P25") (pin "4") (pintype "passive"))
      (node (ref "P26") (pin "4") (pintype "passive"))
      (node (ref "P27") (pin "4") (pintype "passive"))
      (node (ref "P28") (pin "2") (pintype "passive"))
      (node (ref "P7") (pin "3") (pintype "passive"))
      (node (ref "P7") (pin "4") (pintype "passive"))
      (node (ref "R10") (pin "1") (pinfunction "2_1") (pintype "passive"))
      (node (ref "R12") (pin "1") (pinfunction "2_1") (pintype "passive"))
      (node (ref "R15") (pin "1") (pinfunction "2_1") (pintype "passive"))
      (node (ref "R17") (pin "1") (pinfunction "2_1") (pintype "passive"))
      (node (ref "R2") (pin "2") (pinfunction "2_2") (pintype "passive"))
      (node (ref "R21") (pin "1") (pinfunction "2_1") (pintype "passive"))
      (node (ref "R23") (pin "1") (pinfunction "2_1") (pintype "passive"))
      (node (ref "R29") (pin "1") (pinfunction "2_1") (pintype "passive"))
      (node (ref "R3") (pin "2") (pinfunction "2_2") (pintype "passive"))
      (node (ref "R31") (pin "1") (pinfunction "2_1") (pintype "passive"))
      (node (ref "R34") (pin "2") (pinfunction "2_2") (pintype "passive"))
      (node (ref "R35") (pin "2") (pinfunction "2_2") (pintype "passive"))
      (node (ref "R37") (pin "2") (pinfunction "2_2") (pintype "passive"))
      (node (ref "R41") (pin "1") (pinfunction "2_1") (pintype "passive"))
      (node (ref "R45") (pin "2") (pinfunction "2_2") (pintype "passive"))
      (node (ref "R46") (pin "2") (pinfunction "2_2") (pintype "passive"))
      (node (ref "R48") (pin "1") (pinfunction "2_1") (pintype "passive"))
      (node (ref "R5") (pin "1") (pinfunction "2_1") (pintype "passive"))
      (node (ref "R53") (pin "1") (pinfunction "2_1") (pintype "passive"))
      (node (ref "R55") (pin "1") (pinfunction "2_1") (pintype "passive"))
      (node (ref "R59") (pin "1") (pinfunction "2_1") (pintype "passive"))
      (node (ref "R61") (pin "1") (pinfunction "2_1") (pintype "passive"))
      (node (ref "R67") (pin "1") (pinfunction "2_1") (pintype "passive"))
      (node (ref "R69") (pin "1") (pinfunction "2_1") (pintype "passive"))
      (node (ref "R7") (pin "1") (pinfunction "2_1") (pintype "passive"))
      (node (ref "R76") (pin "1") (pinfunction "2_1") (pintype "passive"))
      (node (ref "R78") (pin "1") (pinfunction "2_1") (pintype "passive"))
      (node (ref "R82") (pin "1") (pinfunction "2_1") (pintype "passive"))
      (node (ref "R84") (pin "1") (pinfunction "2_1") (pintype "passive"))
      (node (ref "R86") (pin "2") (pinfunction "2_2") (pintype "passive"))
      (node (ref "R88") (pin "2") (pinfunction "2_2") (pintype "passive"))
      (node (ref "SW1") (pin "1") (pinfunction "Q1_1") (pintype "passive"))
      (node (ref "U1") (pin "107") (pinfunction "VSS_107") (pintype "passive"))
      (node (ref "U1") (pin "120") (pinfunction "VSS_120") (pintype "passive"))
      (node (ref "U1") (pin "130") (pinfunction "VSS_130") (pintype "passive"))
      (node (ref "U1") (pin "16") (pinfunction "VSS_16") (pintype "passive"))
      (node (ref "U1") (pin "31") (pinfunction "VSSA_31") (pintype "passive"))
      (node (ref "U1") (pin "38") (pinfunction "VSS_38") (pintype "passive"))
      (node (ref "U1") (pin "51") (pinfunction "VSS_51") (pintype "passive"))
      (node (ref "U1") (pin "61") (pinfunction "VSS_61") (pintype "passive"))
      (node (ref "U1") (pin "83") (pinfunction "VSS_83") (pintype "passive"))
      (node (ref "U1") (pin "94") (pinfunction "VSS_94") (pintype "passive"))
      (node (ref "U2") (pin "5") (pinfunction "GND_5") (pintype "passive"))
      (node (ref "U3") (pin "2") (pinfunction "GND_2") (pintype "passive"))
      (node (ref "U4") (pin "2") (pinfunction "GND_2") (pintype "passive"))
      (node (ref "U5") (pin "1") (pinfunction "ADJ_1") (pintype "passive"))
      (node (ref "U6") (pin "2") (pinfunction "ADJ_2") (pintype "passive"))
      (node (ref "VD1") (pin "2") (pinfunction "64_2") (pintype "passive"))
      (node (ref "VD10") (pin "2") (pinfunction "64_2") (pintype "passive"))
      (node (ref "VD2") (pin "2") (pinfunction "64_2") (pintype "passive"))
      (node (ref "VD3") (pin "2") (pinfunction "64_2") (pintype "passive"))
      (node (ref "VD4") (pin "2") (pinfunction "64_2") (pintype "passive"))
      (node (ref "VD5") (pin "2") (pinfunction "64_2") (pintype "passive"))
      (node (ref "VD6") (pin "2") (pinfunction "64_2") (pintype "passive"))
      (node (ref "VD7") (pin "2") (pinfunction "64_2") (pintype "passive"))
      (node (ref "VD8") (pin "2") (pinfunction "64_2") (pintype "passive"))
      (node (ref "VD9") (pin "2") (pinfunction "64_2") (pintype "passive"))
      (node (ref "VT3") (pin "3") (pinfunction "11_3") (pintype "passive"))
      (node (ref "VT5") (pin "3") (pinfunction "11_3") (pintype "passive"))
      (node (ref "VT7") (pin "1") (pinfunction "G_1") (pintype "passive"))
    )
    (net (code "38") (name "/GND_EXT") (class "Default")
      (node (ref "P16") (pin "2") (pintype "passive"))
      (node (ref "P17") (pin "2") (pintype "passive"))
      (node (ref "P5") (pin "2") (pintype "passive"))
      (node (ref "P6") (pin "2") (pintype "passive"))
      (node (ref "R11") (pin "2") (pinfunction "2_2") (pintype "passive"))
      (node (ref "R13") (pin "2") (pinfunction "2_2") (pintype "passive"))
      (node (ref "R16") (pin "2") (pinfunction "2_2") (pintype "passive"))
      (node (ref "R18") (pin "2") (pinfunction "2_2") (pintype "passive"))
      (node (ref "R22") (pin "2") (pinfunction "2_2") (pintype "passive"))
      (node (ref "R24") (pin "2") (pinfunction "2_2") (pintype "passive"))
      (node (ref "R30") (pin "2") (pinfunction "2_2") (pintype "passive"))
      (node (ref "R32") (pin "2") (pinfunction "2_2") (pintype "passive"))
      (node (ref "R36") (pin "1") (pinfunction "2_1") (pintype "passive"))
      (node (ref "R38") (pin "1") (pinfunction "2_1") (pintype "passive"))
      (node (ref "R54") (pin "2") (pinfunction "2_2") (pintype "passive"))
      (node (ref "R56") (pin "2") (pinfunction "2_2") (pintype "passive"))
      (node (ref "R6") (pin "2") (pinfunction "2_2") (pintype "passive"))
      (node (ref "R60") (pin "2") (pinfunction "2_2") (pintype "passive"))
      (node (ref "R62") (pin "2") (pinfunction "2_2") (pintype "passive"))
      (node (ref "R68") (pin "2") (pinfunction "2_2") (pintype "passive"))
      (node (ref "R70") (pin "2") (pinfunction "2_2") (pintype "passive"))
      (node (ref "R77") (pin "2") (pinfunction "2_2") (pintype "passive"))
      (node (ref "R79") (pin "2") (pinfunction "2_2") (pintype "passive"))
      (node (ref "R8") (pin "2") (pinfunction "2_2") (pintype "passive"))
      (node (ref "R83") (pin "2") (pinfunction "2_2") (pintype "passive"))
      (node (ref "R85") (pin "2") (pinfunction "2_2") (pintype "passive"))
      (node (ref "R87") (pin "1") (pinfunction "2_1") (pintype "passive"))
      (node (ref "R89") (pin "1") (pinfunction "2_1") (pintype "passive"))
      (node (ref "VT1") (pin "3") (pinfunction "11_3") (pintype "passive"))
      (node (ref "VT2") (pin "3") (pinfunction "11_3") (pintype "passive"))
      (node (ref "VT4") (pin "3") (pinfunction "11_3") (pintype "passive"))
      (node (ref "VT6") (pin "3") (pinfunction "11_3") (pintype "passive"))
    )
    (net (code "39") (name "/I2C1_SCL") (class "Default")
      (node (ref "P14") (pin "3") (pintype "passive"))
      (node (ref "U1") (pin "136") (pinfunction "PB6_136") (pintype "passive"))
    )
    (net (code "40") (name "/I2C1_SDA") (class "Default")
      (node (ref "P14") (pin "4") (pintype "passive"))
      (node (ref "U1") (pin "137") (pinfunction "PB7_137") (pintype "passive"))
    )
    (net (code "41") (name "/INA_1") (class "Default")
      (node (ref "OC1") (pin "5") (pinfunction "1_5") (pintype "passive"))
      (node (ref "U1") (pin "127") (pinfunction "PG12_127") (pintype "passive"))
    )
    (net (code "42") (name "/INA_2") (class "Default")
      (node (ref "OC7") (pin "5") (pinfunction "1_5") (pintype "passive"))
      (node (ref "U1") (pin "117") (pinfunction "PD3_117") (pintype "passive"))
    )
    (net (code "43") (name "/INA_3") (class "Default")
      (node (ref "OC2") (pin "5") (pinfunction "1_5") (pintype "passive"))
      (node (ref "U1") (pin "90") (pinfunction "PG5_90") (pintype "passive"))
    )
    (net (code "44") (name "/INA_4") (class "Default")
      (node (ref "OC8") (pin "5") (pinfunction "1_5") (pintype "passive"))
      (node (ref "U1") (pin "80") (pinfunction "PD11_80") (pintype "passive"))
    )
    (net (code "46") (name "/INB_1") (class "Default")
      (node (ref "OC1") (pin "7") (pinfunction "1_7") (pintype "passive"))
      (node (ref "U1") (pin "126") (pinfunction "PG11_126") (pintype "passive"))
    )
    (net (code "47") (name "/INB_2") (class "Default")
      (node (ref "OC7") (pin "7") (pinfunction "1_7") (pintype "passive"))
      (node (ref "U1") (pin "116") (pinfunction "PD2_116") (pintype "passive"))
    )
    (net (code "48") (name "/INB_3") (class "Default")
      (node (ref "OC2") (pin "7") (pinfunction "1_7") (pintype "passive"))
      (node (ref "U1") (pin "89") (pinfunction "PG4_89") (pintype "passive"))
    )
    (net (code "49") (name "/INB_4") (class "Default")
      (node (ref "OC8") (pin "7") (pinfunction "1_7") (pintype "passive"))
      (node (ref "U1") (pin "79") (pinfunction "PD10_79") (pintype "passive"))
    )
    (net (code "51") (name "/L_LIGHT") (class "Default")
      (node (ref "R26") (pin "1") (pinfunction "2_1") (pintype "passive"))
      (node (ref "U1") (pin "98") (pinfunction "PC8_98") (pintype "passive"))
    )
    (net (code "52") (name "/MPU_CS") (class "Default")
      (node (ref "P15") (pin "4") (pintype "passive"))
      (node (ref "U1") (pin "40") (pinfunction "PA4_40") (pintype "passive"))
    )
    (net (code "53") (name "/NRST") (class "Default")
      (node (ref "C11") (pin "2") (pinfunction "62_2") (pintype "passive"))
      (node (ref "J1") (pin "4") (pintype "passive"))
      (node (ref "R81") (pin "1") (pinfunction "2_1") (pintype "passive"))
      (node (ref "SW1") (pin "3") (pinfunction "Q2_3") (pintype "passive"))
      (node (ref "U1") (pin "25") (pinfunction "NRST_25") (pintype "passive"))
    )
    (net (code "54") (name "/OCB_CS_1") (class "Default")
      (node (ref "OC1") (pin "2") (pinfunction "2_2") (pintype "passive"))
      (node (ref "R1") (pin "1") (pinfunction "1_1") (pintype "passive"))
    )
    (net (code "55") (name "/OCB_CS_2") (class "Default")
      (node (ref "OC7") (pin "2") (pinfunction "2_2") (pintype "passive"))
      (node (ref "R9") (pin "1") (pinfunction "1_1") (pintype "passive"))
    )
    (net (code "56") (name "/OCB_CS_3") (class "Default")
      (node (ref "OC2") (pin "2") (pinfunction "2_2") (pintype "passive"))
      (node (ref "R20") (pin "1") (pinfunction "1_1") (pintype "passive"))
    )
    (net (code "57") (name "/OCB_CS_4") (class "Default")
      (node (ref "OC8") (pin "2") (pinfunction "2_2") (pintype "passive"))
      (node (ref "R33") (pin "1") (pinfunction "1_1") (pintype "passive"))
    )
    (net (code "58") (name "/PF0") (class "Default")
      (node (ref "P10") (pin "1") (pintype "passive"))
      (node (ref "U1") (pin "10") (pinfunction "PF0_10") (pintype "passive"))
    )
    (net (code "59") (name "/PF1") (class "Default")
      (node (ref "P10") (pin "2") (pintype "passive"))
      (node (ref "U1") (pin "11") (pinfunction "PF1_11") (pintype "passive"))
    )
    (net (code "60") (name "/PF2") (class "Default")
      (node (ref "P10") (pin "3") (pintype "passive"))
      (node (ref "U1") (pin "12") (pinfunction "PF2_12") (pintype "passive"))
    )
    (net (code "61") (name "/PF3") (class "Default")
      (node (ref "P10") (pin "4") (pintype "passive"))
      (node (ref "U1") (pin "13") (pinfunction "PF3_13") (pintype "passive"))
    )
    (net (code "62") (name "/PF4") (class "Default")
      (node (ref "P13") (pin "1") (pintype "passive"))
      (node (ref "U1") (pin "14") (pinfunction "PF4_14") (pintype "passive"))
    )
    (net (code "63") (name "/PF5") (class "Default")
      (node (ref "P13") (pin "2") (pintype "passive"))
      (node (ref "U1") (pin "15") (pinfunction "PF5_15") (pintype "passive"))
    )
    (net (code "64") (name "/PWM_1") (class "Default")
      (node (ref "OC3") (pin "1") (pinfunction "1_1") (pintype "passive"))
      (node (ref "U1") (pin "60") (pinfunction "PE9_60") (pintype "passive"))
    )
    (net (code "65") (name "/PWM_2") (class "Default")
      (node (ref "OC9") (pin "1") (pinfunction "1_1") (pintype "passive"))
      (node (ref "U1") (pin "64") (pinfunction "PE11_64") (pintype "passive"))
    )
    (net (code "66") (name "/PWM_3") (class "Default")
      (node (ref "OC4") (pin "1") (pinfunction "1_1") (pintype "passive"))
      (node (ref "U1") (pin "66") (pinfunction "PE13_66") (pintype "passive"))
    )
    (net (code "67") (name "/PWM_4") (class "Default")
      (node (ref "OC10") (pin "1") (pinfunction "1_1") (pintype "passive"))
      (node (ref "U1") (pin "67") (pinfunction "PE14_67") (pintype "passive"))
    )
    (net (code "68") (name "/RCC_OSC32_IN") (class "Default")
      (node (ref "C5") (pin "1") (pinfunction "61_1") (pintype "passive"))
      (node (ref "U1") (pin "8") (pinfunction "PC14_8") (pintype "passive"))
      (node (ref "ZQ1") (pin "1") (pinfunction "10_1") (pintype "passive"))
    )
    (net (code "69") (name "/RCC_OSC32_OUT") (class "Default")
      (node (ref "C12") (pin "1") (pinfunction "61_1") (pintype "passive"))
      (node (ref "U1") (pin "9") (pinfunction "PC15_9") (pintype "passive"))
      (node (ref "ZQ1") (pin "2") (pinfunction "2_2") (pintype "passive"))
    )
    (net (code "70") (name "/RCC_OSC_IN") (class "Default")
      (node (ref "R80") (pin "1") (pinfunction "2_1") (pintype "passive"))
      (node (ref "U1") (pin "23") (pinfunction "PH0_23") (pintype "passive"))
    )
    (net (code "71") (name "/RCC_OSC_OUT") (class "Default")
      (node (ref "C13") (pin "1") (pinfunction "61_1") (pintype "passive"))
      (node (ref "U1") (pin "24") (pinfunction "PH1_24") (pintype "passive"))
      (node (ref "ZQ2") (pin "2") (pinfunction "2_2") (pintype "passive"))
    )
    (net (code "72") (name "/RS485_A") (class "Default")
      (node (ref "R39") (pin "2") (pinfunction "2_2") (pintype "passive"))
      (node (ref "R44") (pin "1") (pinfunction "2_1") (pintype "passive"))
      (node (ref "R52") (pin "2") (pinfunction "2_2") (pintype "passive"))
      (node (ref "U2") (pin "6") (pinfunction "A_6") (pintype "passive"))
      (node (ref "VD1") (pin "1") (pinfunction "63_1") (pintype "passive"))
    )
    (net (code "73") (name "/RS485_B") (class "Default")
      (node (ref "R41") (pin "2") (pinfunction "2_2") (pintype "passive"))
      (node (ref "R44") (pin "2") (pinfunction "2_2") (pintype "passive"))
      (node (ref "R57") (pin "2") (pinfunction "2_2") (pintype "passive"))
      (node (ref "U2") (pin "7") (pinfunction "B_7") (pintype "passive"))
      (node (ref "VD2") (pin "1") (pinfunction "63_1") (pintype "passive"))
    )
    (net (code "74") (name "/R_LIGHT") (class "Default")
      (node (ref "R19") (pin "1") (pinfunction "2_1") (pintype "passive"))
      (node (ref "U1") (pin "99") (pinfunction "PC9_99") (pintype "passive"))
    )
    (net (code "75") (name "/SENSE_1") (class "Default")
      (node (ref "OC1") (pin "15") (pinfunction "3_15") (pintype "passive"))
      (node (ref "R2") (pin "1") (pinfunction "2_1") (pintype "passive"))
      (node (ref "SB1") (pin "2") (pintype "passive"))
    )
    (net (code "76") (name "/SENSE_2") (class "Default")
      (node (ref "OC7") (pin "15") (pinfunction "3_15") (pintype "passive"))
      (node (ref "R45") (pin "1") (pinfunction "2_1") (pintype "passive"))
      (node (ref "SB3") (pin "2") (pintype "passive"))
    )
    (net (code "77") (name "/SENSE_3") (class "Default")
      (node (ref "OC2") (pin "15") (pinfunction "3_15") (pintype "passive"))
      (node (ref "R3") (pin "1") (pinfunction "2_1") (pintype "passive"))
      (node (ref "SB2") (pin "2") (pintype "passive"))
    )
    (net (code "78") (name "/SENSE_4") (class "Default")
      (node (ref "OC8") (pin "15") (pinfunction "3_15") (pintype "passive"))
      (node (ref "R46") (pin "1") (pinfunction "2_1") (pintype "passive"))
      (node (ref "SB4") (pin "2") (pintype "passive"))
    )
    (net (code "79") (name "/SERVO*") (class "Default")
      (node (ref "P24") (pin "2") (pintype "passive"))
      (node (ref "U1") (pin "139") (pinfunction "PB8_139") (pintype "passive"))
    )
    (net (code "80") (name "/SPEED_1") (class "Default")
      (node (ref "OC5") (pin "5") (pinfunction "3_5") (pintype "passive"))
      (node (ref "R35") (pin "1") (pinfunction "2_1") (pintype "passive"))
      (node (ref "U1") (pin "124") (pinfunction "PG9_124") (pintype "passive"))
    )
    (net (code "81") (name "/SPEED_2") (class "Default")
      (node (ref "OC11") (pin "5") (pinfunction "3_5") (pintype "passive"))
      (node (ref "R86") (pin "1") (pinfunction "2_1") (pintype "passive"))
      (node (ref "U1") (pin "114") (pinfunction "PD0_114") (pintype "passive"))
    )
    (net (code "82") (name "/SPEED_3") (class "Default")
      (node (ref "OC6") (pin "5") (pinfunction "3_5") (pintype "passive"))
      (node (ref "R37") (pin "1") (pinfunction "2_1") (pintype "passive"))
      (node (ref "U1") (pin "87") (pinfunction "PG2_87") (pintype "passive"))
    )
    (net (code "83") (name "/SPEED_4") (class "Default")
      (node (ref "OC12") (pin "5") (pinfunction "3_5") (pintype "passive"))
      (node (ref "R88") (pin "1") (pinfunction "2_1") (pintype "passive"))
      (node (ref "U1") (pin "77") (pinfunction "PD8_77") (pintype "passive"))
    )
    (net (code "85") (name "/SPI1_MISO") (class "Default")
      (node (ref "P15") (pin "2") (pintype "passive"))
      (node (ref "U1") (pin "42") (pinfunction "PA6_42") (pintype "passive"))
    )
    (net (code "86") (name "/SPI1_MOSI") (class "Default")
      (node (ref "P15") (pin "1") (pintype "passive"))
      (node (ref "U1") (pin "43") (pinfunction "PA7_43") (pintype "passive"))
    )
    (net (code "87") (name "/SPI1_SCK") (class "Default")
      (node (ref "P15") (pin "3") (pintype "passive"))
      (node (ref "U1") (pin "41") (pinfunction "PA5_41") (pintype "passive"))
    )
    (net (code "88") (name "/SWCLK") (class "Default")
      (node (ref "J1") (pin "2") (pintype "passive"))
      (node (ref "U1") (pin "109") (pinfunction "PA14_109") (pintype "passive"))
    )
    (net (code "89") (name "/SWDIO") (class "Default")
      (node (ref "J1") (pin "3") (pintype "passive"))
      (node (ref "U1") (pin "105") (pinfunction "PA13_105") (pintype "passive"))
    )
    (net (code "90") (name "/TEST_LED") (class "Default")
      (node (ref "R58") (pin "2") (pinfunction "2_2") (pintype "passive"))
      (node (ref "U1") (pin "97") (pinfunction "PC7_97") (pintype "passive"))
    )
    (net (code "91") (name "/UART7_CTS") (class "Default")
      (node (ref "R51") (pin "2") (pinfunction "2_2") (pintype "passive"))
      (node (ref "U1") (pin "21") (pinfunction "PF9_21") (pintype "passive"))
      (node (ref "VD6") (pin "1") (pinfunction "63_1") (pintype "passive"))
    )
    (net (code "92") (name "/UART7_RTS") (class "Default")
      (node (ref "R50") (pin "2") (pinfunction "2_2") (pintype "passive"))
      (node (ref "U1") (pin "20") (pinfunction "PF8_20") (pintype "passive"))
      (node (ref "VD5") (pin "1") (pinfunction "63_1") (pintype "passive"))
    )
    (net (code "93") (name "/UART7_RX") (class "Default")
      (node (ref "R47") (pin "2") (pinfunction "2_2") (pintype "passive"))
      (node (ref "U1") (pin "18") (pinfunction "PF6_18") (pintype "passive"))
      (node (ref "VD4") (pin "1") (pinfunction "63_1") (pintype "passive"))
    )
    (net (code "94") (name "/UART7_TX") (class "Default")
      (node (ref "R49") (pin "2") (pinfunction "2_2") (pintype "passive"))
      (node (ref "U1") (pin "19") (pinfunction "PF7_19") (pintype "passive"))
      (node (ref "VD3") (pin "1") (pinfunction "63_1") (pintype "passive"))
    )
    (net (code "95") (name "/UART8_CTS") (class "Default")
      (node (ref "R48") (pin "2") (pinfunction "2_2") (pintype "passive"))
      (node (ref "U1") (pin "85") (pinfunction "PD14_85") (pintype "passive"))
      (node (ref "U2") (pin "2") (pinfunction "RE_2") (pintype "passive"))
      (node (ref "U2") (pin "3") (pinfunction "DE_3") (pintype "passive"))
    )
    (net (code "96") (name "/UART8_RX") (class "Default")
      (node (ref "R43") (pin "1") (pinfunction "2_1") (pintype "passive"))
      (node (ref "U1") (pin "141") (pinfunction "PE0_141") (pintype "passive"))
      (node (ref "U2") (pin "1") (pinfunction "RO_1") (pintype "passive"))
    )
    (net (code "97") (name "/UART8_TX") (class "Default")
      (node (ref "R42") (pin "1") (pinfunction "2_1") (pintype "passive"))
      (node (ref "U1") (pin "142") (pinfunction "PE1_142") (pintype "passive"))
      (node (ref "U2") (pin "4") (pinfunction "DI_4") (pintype "passive"))
    )
    (net (code "98") (name "/VCAP_1") (class "Default")
      (node (ref "C15") (pin "1") (pinfunction "61_1") (pintype "passive"))
      (node (ref "U1") (pin "71") (pinfunction "VCAP1_71") (pintype "passive"))
    )
    (net (code "99") (name "/VCAP_2") (class "Default")
      (node (ref "C16") (pin "1") (pinfunction "61_1") (pintype "passive"))
      (node (ref "U1") (pin "106") (pinfunction "VCAP2_106") (pintype "passive"))
    )
    (net (code "100") (name "/fromCS_1") (class "Default")
      (node (ref "P1") (pin "1") (pintype "passive"))
      (node (ref "R4") (pin "1") (pinfunction "2_1") (pintype "passive"))
    )
    (net (code "101") (name "/fromCS_2") (class "Default")
      (node (ref "P8") (pin "1") (pintype "passive"))
      (node (ref "R14") (pin "1") (pinfunction "2_1") (pintype "passive"))
    )
    (net (code "102") (name "/fromCS_3") (class "Default")
      (node (ref "P2") (pin "1") (pintype "passive"))
      (node (ref "R27") (pin "1") (pinfunction "2_1") (pintype "passive"))
    )
    (net (code "103") (name "/fromCS_4") (class "Default")
      (node (ref "P9") (pin "1") (pintype "passive"))
      (node (ref "R40") (pin "1") (pinfunction "2_1") (pintype "passive"))
    )
    (net (code "104") (name "/fromENC_1") (class "Default")
      (node (ref "OC5") (pin "3") (pinfunction "1_3") (pintype "passive"))
      (node (ref "P3") (pin "4") (pintype "passive"))
    )
    (net (code "105") (name "/fromENC_2") (class "Default")
      (node (ref "OC11") (pin "3") (pinfunction "1_3") (pintype "passive"))
      (node (ref "P11") (pin "4") (pintype "passive"))
    )
    (net (code "106") (name "/fromENC_3") (class "Default")
      (node (ref "OC6") (pin "3") (pinfunction "1_3") (pintype "passive"))
      (node (ref "P4") (pin "4") (pintype "passive"))
    )
    (net (code "107") (name "/fromENC_4") (class "Default")
      (node (ref "OC12") (pin "3") (pinfunction "1_3") (pintype "passive"))
      (node (ref "P12") (pin "4") (pintype "passive"))
    )
    (net (code "108") (name "/toENC_1") (class "Default")
      (node (ref "OC5") (pin "7") (pinfunction "3_7") (pintype "passive"))
      (node (ref "P3") (pin "3") (pintype "passive"))
      (node (ref "R30") (pin "1") (pinfunction "2_1") (pintype "passive"))
    )
    (net (code "109") (name "/toENC_2") (class "Default")
      (node (ref "OC11") (pin "7") (pinfunction "3_7") (pintype "passive"))
      (node (ref "P11") (pin "3") (pintype "passive"))
      (node (ref "R83") (pin "1") (pinfunction "2_1") (pintype "passive"))
    )
    (net (code "110") (name "/toENC_3") (class "Default")
      (node (ref "OC6") (pin "7") (pinfunction "3_7") (pintype "passive"))
      (node (ref "P4") (pin "3") (pintype "passive"))
      (node (ref "R32") (pin "1") (pinfunction "2_1") (pintype "passive"))
    )
    (net (code "111") (name "/toENC_4") (class "Default")
      (node (ref "OC12") (pin "7") (pinfunction "3_7") (pintype "passive"))
      (node (ref "P12") (pin "3") (pintype "passive"))
      (node (ref "R85") (pin "1") (pinfunction "2_1") (pintype "passive"))
    )
    (net (code "112") (name "/toEN_1") (class "Default")
      (node (ref "OC1") (pin "13") (pinfunction "3_13") (pintype "passive"))
      (node (ref "P1") (pin "2") (pintype "passive"))
      (node (ref "R6") (pin "1") (pinfunction "2_1") (pintype "passive"))
    )
    (net (code "113") (name "/toEN_2") (class "Default")
      (node (ref "OC7") (pin "13") (pinfunction "3_13") (pintype "passive"))
      (node (ref "P8") (pin "2") (pintype "passive"))
      (node (ref "R54") (pin "1") (pinfunction "2_1") (pintype "passive"))
    )
    (net (code "114") (name "/toEN_3") (class "Default")
      (node (ref "OC2") (pin "13") (pinfunction "3_13") (pintype "passive"))
      (node (ref "P2") (pin "2") (pintype "passive"))
      (node (ref "R8") (pin "1") (pinfunction "2_1") (pintype "passive"))
    )
    (net (code "115") (name "/toEN_4") (class "Default")
      (node (ref "OC8") (pin "13") (pinfunction "3_13") (pintype "passive"))
      (node (ref "P9") (pin "2") (pintype "passive"))
      (node (ref "R56") (pin "1") (pinfunction "2_1") (pintype "passive"))
    )
    (net (code "116") (name "/toINA_1") (class "Default")
      (node (ref "OC1") (pin "11") (pinfunction "3_11") (pintype "passive"))
      (node (ref "P1") (pin "3") (pintype "passive"))
      (node (ref "R11") (pin "1") (pinfunction "2_1") (pintype "passive"))
    )
    (net (code "117") (name "/toINA_2") (class "Default")
      (node (ref "OC7") (pin "11") (pinfunction "3_11") (pintype "passive"))
      (node (ref "P8") (pin "3") (pintype "passive"))
      (node (ref "R60") (pin "1") (pinfunction "2_1") (pintype "passive"))
    )
    (net (code "118") (name "/toINA_3") (class "Default")
      (node (ref "OC2") (pin "11") (pinfunction "3_11") (pintype "passive"))
      (node (ref "P2") (pin "3") (pintype "passive"))
      (node (ref "R13") (pin "1") (pinfunction "2_1") (pintype "passive"))
    )
    (net (code "119") (name "/toINA_4") (class "Default")
      (node (ref "OC8") (pin "11") (pinfunction "3_11") (pintype "passive"))
      (node (ref "P9") (pin "3") (pintype "passive"))
      (node (ref "R62") (pin "1") (pinfunction "2_1") (pintype "passive"))
    )
    (net (code "120") (name "/toINB_1") (class "Default")
      (node (ref "OC1") (pin "9") (pinfunction "3_9") (pintype "passive"))
      (node (ref "P1") (pin "4") (pintype "passive"))
      (node (ref "R16") (pin "1") (pinfunction "2_1") (pintype "passive"))
    )
    (net (code "121") (name "/toINB_2") (class "Default")
      (node (ref "OC7") (pin "9") (pinfunction "3_9") (pintype "passive"))
      (node (ref "P8") (pin "4") (pintype "passive"))
      (node (ref "R68") (pin "1") (pinfunction "2_1") (pintype "passive"))
    )
    (net (code "122") (name "/toINB_3") (class "Default")
      (node (ref "OC2") (pin "9") (pinfunction "3_9") (pintype "passive"))
      (node (ref "P2") (pin "4") (pintype "passive"))
      (node (ref "R18") (pin "1") (pinfunction "2_1") (pintype "passive"))
    )
    (net (code "123") (name "/toINB_4") (class "Default")
      (node (ref "OC8") (pin "9") (pinfunction "3_9") (pintype "passive"))
      (node (ref "P9") (pin "4") (pintype "passive"))
      (node (ref "R70") (pin "1") (pinfunction "2_1") (pintype "passive"))
    )
    (net (code "124") (name "/toPWM_1") (class "Default")
      (node (ref "OC3") (pin "3") (pinfunction "3_3") (pintype "passive"))
      (node (ref "P3") (pin "1") (pintype "passive"))
      (node (ref "R22") (pin "1") (pinfunction "2_1") (pintype "passive"))
    )
    (net (code "125") (name "/toPWM_2") (class "Default")
      (node (ref "OC9") (pin "3") (pinfunction "3_3") (pintype "passive"))
      (node (ref "P11") (pin "1") (pintype "passive"))
      (node (ref "R77") (pin "1") (pinfunction "2_1") (pintype "passive"))
    )
    (net (code "126") (name "/toPWM_3") (class "Default")
      (node (ref "OC4") (pin "3") (pinfunction "3_3") (pintype "passive"))
      (node (ref "P4") (pin "1") (pintype "passive"))
      (node (ref "R24") (pin "1") (pinfunction "2_1") (pintype "passive"))
    )
    (net (code "127") (name "/toPWM_4") (class "Default")
      (node (ref "OC10") (pin "3") (pinfunction "3_3") (pintype "passive"))
      (node (ref "P12") (pin "1") (pintype "passive"))
      (node (ref "R79") (pin "1") (pinfunction "2_1") (pintype "passive"))
    )
    (net (code "128") (name "Net-(C6-61)") (class "Default")
      (node (ref "C6") (pin "1") (pinfunction "61_1") (pintype "passive"))
      (node (ref "R80") (pin "2") (pinfunction "2_2") (pintype "passive"))
      (node (ref "ZQ2") (pin "1") (pinfunction "10_1") (pintype "passive"))
    )
    (net (code "129") (name "Net-(LED1-5)") (class "Default")
      (node (ref "LED1") (pin "1") (pinfunction "5_1") (pintype "passive"))
      (node (ref "R42") (pin "2") (pinfunction "2_2") (pintype "passive"))
    )
    (net (code "130") (name "Net-(LED2-5)") (class "Default")
      (node (ref "LED2") (pin "1") (pinfunction "5_1") (pintype "passive"))
      (node (ref "R43") (pin "2") (pinfunction "2_2") (pintype "passive"))
    )
    (net (code "131") (name "Net-(LED3-5)") (class "Default")
      (node (ref "LED3") (pin "1") (pinfunction "5_1") (pintype "passive"))
      (node (ref "R58") (pin "1") (pinfunction "2_1") (pintype "passive"))
    )
    (net (code "132") (name "Net-(LED4-5)") (class "Default")
      (node (ref "LED4") (pin "1") (pinfunction "5_1") (pintype "passive"))
      (node (ref "R66") (pin "1") (pinfunction "2_1") (pintype "passive"))
    )
    (net (code "133") (name "Net-(LED5-5)") (class "Default")
      (node (ref "LED5") (pin "1") (pinfunction "5_1") (pintype "passive"))
      (node (ref "R71") (pin "1") (pinfunction "2_1") (pintype "passive"))
    )
    (net (code "134") (name "Net-(LED6-5)") (class "Default")
      (node (ref "LED6") (pin "1") (pinfunction "5_1") (pintype "passive"))
      (node (ref "R75") (pin "1") (pinfunction "2_1") (pintype "passive"))
    )
    (net (code "135") (name "Net-(OC1B-2)") (class "Default")
      (node (ref "OC1") (pin "4") (pinfunction "2_4") (pintype "passive"))
      (node (ref "R5") (pin "2") (pinfunction "2_2") (pintype "passive"))
    )
    (net (code "136") (name "Net-(OC1C-2)") (class "Default")
      (node (ref "OC1") (pin "6") (pinfunction "2_6") (pintype "passive"))
      (node (ref "R10") (pin "2") (pinfunction "2_2") (pintype "passive"))
    )
    (net (code "137") (name "Net-(OC1D-2)") (class "Default")
      (node (ref "OC1") (pin "8") (pinfunction "2_8") (pintype "passive"))
      (node (ref "R15") (pin "2") (pinfunction "2_2") (pintype "passive"))
    )
    (net (code "138") (name "Net-(OC2B-2)") (class "Default")
      (node (ref "OC2") (pin "4") (pinfunction "2_4") (pintype "passive"))
      (node (ref "R7") (pin "2") (pinfunction "2_2") (pintype "passive"))
    )
    (net (code "139") (name "Net-(OC2C-2)") (class "Default")
      (node (ref "OC2") (pin "6") (pinfunction "2_6") (pintype "passive"))
      (node (ref "R12") (pin "2") (pinfunction "2_2") (pintype "passive"))
    )
    (net (code "140") (name "Net-(OC2D-2)") (class "Default")
      (node (ref "OC2") (pin "8") (pinfunction "2_8") (pintype "passive"))
      (node (ref "R17") (pin "2") (pinfunction "2_2") (pintype "passive"))
    )
    (net (code "141") (name "Net-(OC3-Pad2)") (class "Default")
      (node (ref "OC3") (pin "2") (pinfunction "2_2") (pintype "passive"))
      (node (ref "R21") (pin "2") (pinfunction "2_2") (pintype "passive"))
    )
    (net (code "142") (name "Net-(OC4-Pad2)") (class "Default")
      (node (ref "OC4") (pin "2") (pinfunction "2_2") (pintype "passive"))
      (node (ref "R23") (pin "2") (pinfunction "2_2") (pintype "passive"))
    )
    (net (code "143") (name "Net-(OC5-Pad2)") (class "Default")
      (node (ref "OC5") (pin "2") (pinfunction "2_2") (pintype "passive"))
      (node (ref "R29") (pin "2") (pinfunction "2_2") (pintype "passive"))
    )
    (net (code "144") (name "Net-(OC5B-3-Pad4)") (class "Default")
      (node (ref "OC5") (pin "4") (pinfunction "3_4") (pintype "passive"))
      (node (ref "R36") (pin "2") (pinfunction "2_2") (pintype "passive"))
    )
    (net (code "145") (name "Net-(OC6-Pad2)") (class "Default")
      (node (ref "OC6") (pin "2") (pinfunction "2_2") (pintype "passive"))
      (node (ref "R31") (pin "2") (pinfunction "2_2") (pintype "passive"))
    )
    (net (code "146") (name "Net-(OC6B-3-Pad4)") (class "Default")
      (node (ref "OC6") (pin "4") (pinfunction "3_4") (pintype "passive"))
      (node (ref "R38") (pin "2") (pinfunction "2_2") (pintype "passive"))
    )
    (net (code "147") (name "Net-(OC7B-2)") (class "Default")
      (node (ref "OC7") (pin "4") (pinfunction "2_4") (pintype "passive"))
      (node (ref "R53") (pin "2") (pinfunction "2_2") (pintype "passive"))
    )
    (net (code "148") (name "Net-(OC7C-2)") (class "Default")
      (node (ref "OC7") (pin "6") (pinfunction "2_6") (pintype "passive"))
      (node (ref "R59") (pin "2") (pinfunction "2_2") (pintype "passive"))
    )
    (net (code "149") (name "Net-(OC7D-2)") (class "Default")
      (node (ref "OC7") (pin "8") (pinfunction "2_8") (pintype "passive"))
      (node (ref "R67") (pin "2") (pinfunction "2_2") (pintype "passive"))
    )
    (net (code "150") (name "Net-(OC8B-2)") (class "Default")
      (node (ref "OC8") (pin "4") (pinfunction "2_4") (pintype "passive"))
      (node (ref "R55") (pin "2") (pinfunction "2_2") (pintype "passive"))
    )
    (net (code "151") (name "Net-(OC8C-2)") (class "Default")
      (node (ref "OC8") (pin "6") (pinfunction "2_6") (pintype "passive"))
      (node (ref "R61") (pin "2") (pinfunction "2_2") (pintype "passive"))
    )
    (net (code "152") (name "Net-(OC8D-2)") (class "Default")
      (node (ref "OC8") (pin "8") (pinfunction "2_8") (pintype "passive"))
      (node (ref "R69") (pin "2") (pinfunction "2_2") (pintype "passive"))
    )
    (net (code "153") (name "Net-(OC9-Pad2)") (class "Default")
      (node (ref "OC9") (pin "2") (pinfunction "2_2") (pintype "passive"))
      (node (ref "R76") (pin "2") (pinfunction "2_2") (pintype "passive"))
    )
    (net (code "154") (name "Net-(OC10-Pad2)") (class "Default")
      (node (ref "OC10") (pin "2") (pinfunction "2_2") (pintype "passive"))
      (node (ref "R78") (pin "2") (pinfunction "2_2") (pintype "passive"))
    )
    (net (code "155") (name "Net-(OC11-Pad2)") (class "Default")
      (node (ref "OC11") (pin "2") (pinfunction "2_2") (pintype "passive"))
      (node (ref "R82") (pin "2") (pinfunction "2_2") (pintype "passive"))
    )
    (net (code "156") (name "Net-(OC11B-3-Pad4)") (class "Default")
      (node (ref "OC11") (pin "4") (pinfunction "3_4") (pintype "passive"))
      (node (ref "R87") (pin "2") (pinfunction "2_2") (pintype "passive"))
    )
    (net (code "157") (name "Net-(OC12-Pad2)") (class "Default")
      (node (ref "OC12") (pin "2") (pinfunction "2_2") (pintype "passive"))
      (node (ref "R84") (pin "2") (pinfunction "2_2") (pintype "passive"))
    )
    (net (code "158") (name "Net-(OC12B-3-Pad4)") (class "Default")
      (node (ref "OC12") (pin "4") (pinfunction "3_4") (pintype "passive"))
      (node (ref "R89") (pin "2") (pinfunction "2_2") (pintype "passive"))
    )
    (net (code "159") (name "Net-(P19-Pad1)") (class "Default")
      (node (ref "P19") (pin "1") (pintype "passive"))
      (node (ref "R25") (pin "2") (pinfunction "2_2") (pintype "passive"))
    )
    (net (code "160") (name "Net-(P21-Pad1)") (class "Default")
      (node (ref "P21") (pin "1") (pintype "passive"))
      (node (ref "R28") (pin "2") (pinfunction "2_2") (pintype "passive"))
    )
    (net (code "161") (name "Net-(P23-Pad1)") (class "Default")
      (node (ref "P23") (pin "1") (pintype "passive"))
      (node (ref "R47") (pin "1") (pinfunction "2_1") (pintype "passive"))
    )
    (net (code "162") (name "Net-(P23-Pad2)") (class "Default")
      (node (ref "P23") (pin "2") (pintype "passive"))
      (node (ref "R49") (pin "1") (pinfunction "2_1") (pintype "passive"))
    )
    (net (code "163") (name "Net-(P23-Pad3)") (class "Default")
      (node (ref "P23") (pin "3") (pintype "passive"))
      (node (ref "R50") (pin "1") (pinfunction "2_1") (pintype "passive"))
    )
    (net (code "164") (name "Net-(P23-Pad4)") (class "Default")
      (node (ref "P23") (pin "4") (pintype "passive"))
      (node (ref "R51") (pin "1") (pinfunction "2_1") (pintype "passive"))
    )
    (net (code "165") (name "Net-(P25-Pad2)") (class "Default")
      (node (ref "P25") (pin "2") (pintype "passive"))
      (node (ref "R52") (pin "1") (pinfunction "2_1") (pintype "passive"))
    )
    (net (code "166") (name "Net-(P25-Pad3)") (class "Default")
      (node (ref "P25") (pin "3") (pintype "passive"))
      (node (ref "R57") (pin "1") (pinfunction "2_1") (pintype "passive"))
    )
    (net (code "167") (name "Net-(P26-Pad1)") (class "Default")
      (node (ref "P26") (pin "1") (pintype "passive"))
      (node (ref "R64") (pin "1") (pinfunction "2_1") (pintype "passive"))
    )
    (net (code "168") (name "Net-(P26-Pad2)") (class "Default")
      (node (ref "P26") (pin "2") (pintype "passive"))
      (node (ref "R65") (pin "1") (pinfunction "2_1") (pintype "passive"))
    )
    (net (code "169") (name "Net-(P27-Pad1)") (class "Default")
      (node (ref "P27") (pin "1") (pintype "passive"))
      (node (ref "R73") (pin "1") (pinfunction "2_1") (pintype "passive"))
    )
    (net (code "170") (name "Net-(P27-Pad2)") (class "Default")
      (node (ref "P27") (pin "2") (pintype "passive"))
      (node (ref "R74") (pin "1") (pinfunction "2_1") (pintype "passive"))
    )
    (net (code "171") (name "Net-(U1-BOOT0)") (class "Default")
      (node (ref "R34") (pin "1") (pinfunction "2_1") (pintype "passive"))
      (node (ref "U1") (pin "138") (pinfunction "BOOT0_138") (pintype "passive"))
    )
    (net (code "172") (name "Net-(U3-CANH)") (class "Default")
      (node (ref "R63") (pin "1") (pinfunction "2_1") (pintype "passive"))
      (node (ref "R64") (pin "2") (pinfunction "2_2") (pintype "passive"))
      (node (ref "U3") (pin "7") (pinfunction "CANH_7") (pintype "passive"))
      (node (ref "VD7") (pin "1") (pinfunction "63_1") (pintype "passive"))
    )
    (net (code "173") (name "Net-(U3-CANL)") (class "Default")
      (node (ref "R63") (pin "2") (pinfunction "2_2") (pintype "passive"))
      (node (ref "R65") (pin "2") (pinfunction "2_2") (pintype "passive"))
      (node (ref "U3") (pin "6") (pinfunction "CANL_6") (pintype "passive"))
      (node (ref "VD8") (pin "1") (pinfunction "63_1") (pintype "passive"))
    )
    (net (code "174") (name "Net-(U4-CANH)") (class "Default")
      (node (ref "R72") (pin "1") (pinfunction "2_1") (pintype "passive"))
      (node (ref "R73") (pin "2") (pinfunction "2_2") (pintype "passive"))
      (node (ref "U4") (pin "7") (pinfunction "CANH_7") (pintype "passive"))
      (node (ref "VD9") (pin "1") (pinfunction "63_1") (pintype "passive"))
    )
    (net (code "175") (name "Net-(U4-CANL)") (class "Default")
      (node (ref "R72") (pin "2") (pinfunction "2_2") (pintype "passive"))
      (node (ref "R74") (pin "2") (pinfunction "2_2") (pintype "passive"))
      (node (ref "U4") (pin "6") (pinfunction "CANL_6") (pintype "passive"))
      (node (ref "VD10") (pin "1") (pinfunction "63_1") (pintype "passive"))
    )
    (net (code "176") (name "Net-(VT1-9)") (class "Default")
      (node (ref "R1") (pin "2") (pintype "passive"))
      (node (ref "R1") (pin "3") (pinfunction "3_3") (pintype "passive"))
      (node (ref "VT1") (pin "1") (pinfunction "9_1") (pintype "passive"))
    )
    (net (code "177") (name "Net-(VT1-10)") (class "Default")
      (node (ref "R4") (pin "2") (pinfunction "2_2") (pintype "passive"))
      (node (ref "VT1") (pin "2") (pinfunction "10_2") (pintype "passive"))
    )
    (net (code "178") (name "Net-(VT2-9)") (class "Default")
      (node (ref "R9") (pin "2") (pintype "passive"))
      (node (ref "R9") (pin "3") (pinfunction "3_3") (pintype "passive"))
      (node (ref "VT2") (pin "1") (pinfunction "9_1") (pintype "passive"))
    )
    (net (code "179") (name "Net-(VT2-10)") (class "Default")
      (node (ref "R14") (pin "2") (pinfunction "2_2") (pintype "passive"))
      (node (ref "VT2") (pin "2") (pinfunction "10_2") (pintype "passive"))
    )
    (net (code "180") (name "Net-(VT3-9)") (class "Default")
      (node (ref "R25") (pin "1") (pinfunction "2_1") (pintype "passive"))
      (node (ref "VT3") (pin "1") (pinfunction "9_1") (pintype "passive"))
    )
    (net (code "181") (name "Net-(VT3-10)") (class "Default")
      (node (ref "R19") (pin "2") (pinfunction "2_2") (pintype "passive"))
      (node (ref "VT3") (pin "2") (pinfunction "10_2") (pintype "passive"))
    )
    (net (code "182") (name "Net-(VT4-9)") (class "Default")
      (node (ref "R20") (pin "2") (pintype "passive"))
      (node (ref "R20") (pin "3") (pinfunction "3_3") (pintype "passive"))
      (node (ref "VT4") (pin "1") (pinfunction "9_1") (pintype "passive"))
    )
    (net (code "183") (name "Net-(VT4-10)") (class "Default")
      (node (ref "R27") (pin "2") (pinfunction "2_2") (pintype "passive"))
      (node (ref "VT4") (pin "2") (pinfunction "10_2") (pintype "passive"))
    )
    (net (code "184") (name "Net-(VT5-9)") (class "Default")
      (node (ref "R28") (pin "1") (pinfunction "2_1") (pintype "passive"))
      (node (ref "VT5") (pin "1") (pinfunction "9_1") (pintype "passive"))
    )
    (net (code "185") (name "Net-(VT5-10)") (class "Default")
      (node (ref "R26") (pin "2") (pinfunction "2_2") (pintype "passive"))
      (node (ref "VT5") (pin "2") (pinfunction "10_2") (pintype "passive"))
    )
    (net (code "186") (name "Net-(VT6-9)") (class "Default")
      (node (ref "R33") (pin "2") (pintype "passive"))
      (node (ref "R33") (pin "3") (pinfunction "3_3") (pintype "passive"))
      (node (ref "VT6") (pin "1") (pinfunction "9_1") (pintype "passive"))
    )
    (net (code "187") (name "Net-(VT6-10)") (class "Default")
      (node (ref "R40") (pin "2") (pinfunction "2_2") (pintype "passive"))
      (node (ref "VT6") (pin "2") (pinfunction "10_2") (pintype "passive"))
    )
    (net (code "188") (name "Net-(VT7-D)") (class "Default")
      (node (ref "P28") (pin "1") (pintype "passive"))
      (node (ref "VT7") (pin "2") (pinfunction "D_2") (pintype "passive"))
    )
    (net (code "189") (name "unconnected-(P3-Pad2)") (class "Default")
      (node (ref "P3") (pin "2") (pintype "passive+no_connect"))
    )
    (net (code "190") (name "unconnected-(P4-Pad2)") (class "Default")
      (node (ref "P4") (pin "2") (pintype "passive+no_connect"))
    )
    (net (code "191") (name "unconnected-(P11-Pad2)") (class "Default")
      (node (ref "P11") (pin "2") (pintype "passive+no_connect"))
    )
    (net (code "192") (name "unconnected-(P12-Pad2)") (class "Default")
      (node (ref "P12") (pin "2") (pintype "passive+no_connect"))
    )
    (net (code "193") (name "unconnected-(SW1-Q1-Pad2)") (class "Default")
      (node (ref "SW1") (pin "2") (pinfunction "Q1_2") (pintype "passive"))
    )
    (net (code "194") (name "unconnected-(SW1-Q2-Pad4)") (class "Default")
      (node (ref "SW1") (pin "4") (pinfunction "Q2_4") (pintype "passive"))
    )
    (net (code "195") (name "unconnected-(U1-PA8-Pad100)") (class "Default")
      (node (ref "U1") (pin "100") (pinfunction "PA8_100") (pintype "passive+no_connect"))
    )
    (net (code "196") (name "unconnected-(U1-PA15-Pad110)") (class "Default")
      (node (ref "U1") (pin "110") (pinfunction "PA15_110") (pintype "passive+no_connect"))
    )
    (net (code "197") (name "unconnected-(U1-PB2-Pad48)") (class "Default")
      (node (ref "U1") (pin "48") (pinfunction "PB2_48") (pintype "passive+no_connect"))
    )
    (net (code "198") (name "unconnected-(U1-PB3-Pad133)") (class "Default")
      (node (ref "U1") (pin "133") (pinfunction "PB3_133") (pintype "passive+no_connect"))
    )
    (net (code "199") (name "unconnected-(U1-PB4-Pad134)") (class "Default")
      (node (ref "U1") (pin "134") (pinfunction "PB4_134") (pintype "passive+no_connect"))
    )
    (net (code "200") (name "unconnected-(U1-PB5-Pad135)") (class "Default")
      (node (ref "U1") (pin "135") (pinfunction "PB5_135") (pintype "passive+no_connect"))
    )
    (net (code "201") (name "unconnected-(U1-PB9-Pad140)") (class "Default")
      (node (ref "U1") (pin "140") (pinfunction "PB9_140") (pintype "passive+no_connect"))
    )
    (net (code "202") (name "unconnected-(U1-PB10-Pad69)") (class "Default")
      (node (ref "U1") (pin "69") (pinfunction "PB10_69") (pintype "passive+no_connect"))
    )
    (net (code "203") (name "unconnected-(U1-PB11-Pad70)") (class "Default")
      (node (ref "U1") (pin "70") (pinfunction "PB11_70") (pintype "passive+no_connect"))
    )
    (net (code "204") (name "unconnected-(U1-PC0-Pad26)") (class "Default")
      (node (ref "U1") (pin "26") (pinfunction "PC0_26") (pintype "passive+no_connect"))
    )
    (net (code "205") (name "unconnected-(U1-PC1-Pad27)") (class "Default")
      (node (ref "U1") (pin "27") (pinfunction "PC1_27") (pintype "passive+no_connect"))
    )
    (net (code "206") (name "unconnected-(U1-PC2-Pad28)") (class "Default")
      (node (ref "U1") (pin "28") (pinfunction "PC2_28") (pintype "passive+no_connect"))
    )
    (net (code "207") (name "unconnected-(U1-PC3-Pad29)") (class "Default")
      (node (ref "U1") (pin "29") (pinfunction "PC3_29") (pintype "passive+no_connect"))
    )
    (net (code "208") (name "unconnected-(U1-PC4-Pad44)") (class "Default")
      (node (ref "U1") (pin "44") (pinfunction "PC4_44") (pintype "passive+no_connect"))
    )
    (net (code "209") (name "unconnected-(U1-PC6-Pad96)") (class "Default")
      (node (ref "U1") (pin "96") (pinfunction "PC6_96") (pintype "passive+no_connect"))
    )
    (net (code "210") (name "unconnected-(U1-PC10-Pad111)") (class "Default")
      (node (ref "U1") (pin "111") (pinfunction "PC10_111") (pintype "passive+no_connect"))
    )
    (net (code "211") (name "unconnected-(U1-PC11-Pad112)") (class "Default")
      (node (ref "U1") (pin "112") (pinfunction "PC11_112") (pintype "passive+no_connect"))
    )
    (net (code "212") (name "unconnected-(U1-PC12-Pad113)") (class "Default")
      (node (ref "U1") (pin "113") (pinfunction "PC12_113") (pintype "passive"))
    )
    (net (code "213") (name "unconnected-(U1-PC13-Pad7)") (class "Default")
      (node (ref "U1") (pin "7") (pinfunction "PC13_7") (pintype "passive+no_connect"))
    )
    (net (code "214") (name "unconnected-(U1-PD6-Pad122)") (class "Default")
      (node (ref "U1") (pin "122") (pinfunction "PD6_122") (pintype "passive+no_connect"))
    )
    (net (code "215") (name "unconnected-(U1-PD7-Pad123)") (class "Default")
      (node (ref "U1") (pin "123") (pinfunction "PD7_123") (pintype "passive+no_connect"))
    )
    (net (code "216") (name "unconnected-(U1-PD15-Pad86)") (class "Default")
      (node (ref "U1") (pin "86") (pinfunction "PD15_86") (pintype "passive+no_connect"))
    )
    (net (code "217") (name "unconnected-(U1-PE2-Pad1)") (class "Default")
      (node (ref "U1") (pin "1") (pinfunction "PE2_1") (pintype "passive+no_connect"))
    )
    (net (code "218") (name "unconnected-(U1-PE3-Pad2)") (class "Default")
      (node (ref "U1") (pin "2") (pinfunction "PE3_2") (pintype "passive+no_connect"))
    )
    (net (code "219") (name "unconnected-(U1-PE4-Pad3)") (class "Default")
      (node (ref "U1") (pin "3") (pinfunction "PE4_3") (pintype "passive+no_connect"))
    )
    (net (code "220") (name "unconnected-(U1-PE5-Pad4)") (class "Default")
      (node (ref "U1") (pin "4") (pinfunction "PE5_4") (pintype "passive+no_connect"))
    )
    (net (code "221") (name "unconnected-(U1-PE6-Pad5)") (class "Default")
      (node (ref "U1") (pin "5") (pinfunction "PE6_5") (pintype "passive+no_connect"))
    )
    (net (code "222") (name "unconnected-(U1-PE7-Pad58)") (class "Default")
      (node (ref "U1") (pin "58") (pinfunction "PE7_58") (pintype "passive+no_connect"))
    )
    (net (code "223") (name "unconnected-(U1-PE8-Pad59)") (class "Default")
      (node (ref "U1") (pin "59") (pinfunction "PE8_59") (pintype "passive+no_connect"))
    )
    (net (code "224") (name "unconnected-(U1-PE10-Pad63)") (class "Default")
      (node (ref "U1") (pin "63") (pinfunction "PE10_63") (pintype "passive"))
    )
    (net (code "225") (name "unconnected-(U1-PE12-Pad65)") (class "Default")
      (node (ref "U1") (pin "65") (pinfunction "PE12_65") (pintype "passive"))
    )
    (net (code "226") (name "unconnected-(U1-PE15-Pad68)") (class "Default")
      (node (ref "U1") (pin "68") (pinfunction "PE15_68") (pintype "passive+no_connect"))
    )
    (net (code "227") (name "unconnected-(U1-PF10-Pad22)") (class "Default")
      (node (ref "U1") (pin "22") (pinfunction "PF10_22") (pintype "passive+no_connect"))
    )
    (net (code "228") (name "unconnected-(U1-PF11-Pad49)") (class "Default")
      (node (ref "U1") (pin "49") (pinfunction "PF11_49") (pintype "passive+no_connect"))
    )
    (net (code "229") (name "unconnected-(U1-PF12-Pad50)") (class "Default")
      (node (ref "U1") (pin "50") (pinfunction "PF12_50") (pintype "passive+no_connect"))
    )
    (net (code "230") (name "unconnected-(U1-PF13-Pad53)") (class "Default")
      (node (ref "U1") (pin "53") (pinfunction "PF13_53") (pintype "passive+no_connect"))
    )
    (net (code "231") (name "unconnected-(U1-PF14-Pad54)") (class "Default")
      (node (ref "U1") (pin "54") (pinfunction "PF14_54") (pintype "passive+no_connect"))
    )
    (net (code "232") (name "unconnected-(U1-PF15-Pad55)") (class "Default")
      (node (ref "U1") (pin "55") (pinfunction "PF15_55") (pintype "passive+no_connect"))
    )
    (net (code "233") (name "unconnected-(U1-PG0-Pad56)") (class "Default")
      (node (ref "U1") (pin "56") (pinfunction "PG0_56") (pintype "passive+no_connect"))
    )
    (net (code "234") (name "unconnected-(U1-PG1-Pad57)") (class "Default")
      (node (ref "U1") (pin "57") (pinfunction "PG1_57") (pintype "passive+no_connect"))
    )
    (net (code "235") (name "unconnected-(U1-PG8-Pad93)") (class "Default")
      (node (ref "U1") (pin "93") (pinfunction "PG8_93") (pintype "passive+no_connect"))
    )
    (net (code "236") (name "unconnected-(U1-PG15-Pad132)") (class "Default")
      (node (ref "U1") (pin "132") (pinfunction "PG15_132") (pintype "passive+no_connect"))
    )
    (net (code "237") (name "unconnected-(U1-VDD_SDMMC-Pad121)") (class "Default")
      (node (ref "U1") (pin "121") (pinfunction "VDD_SDMMC_121") (pintype "passive+no_connect"))
    )
  )
)
